# mainBoard_GTernal_1-1_v27.net
KiCad netlist of a schematic drawn in EAGLE
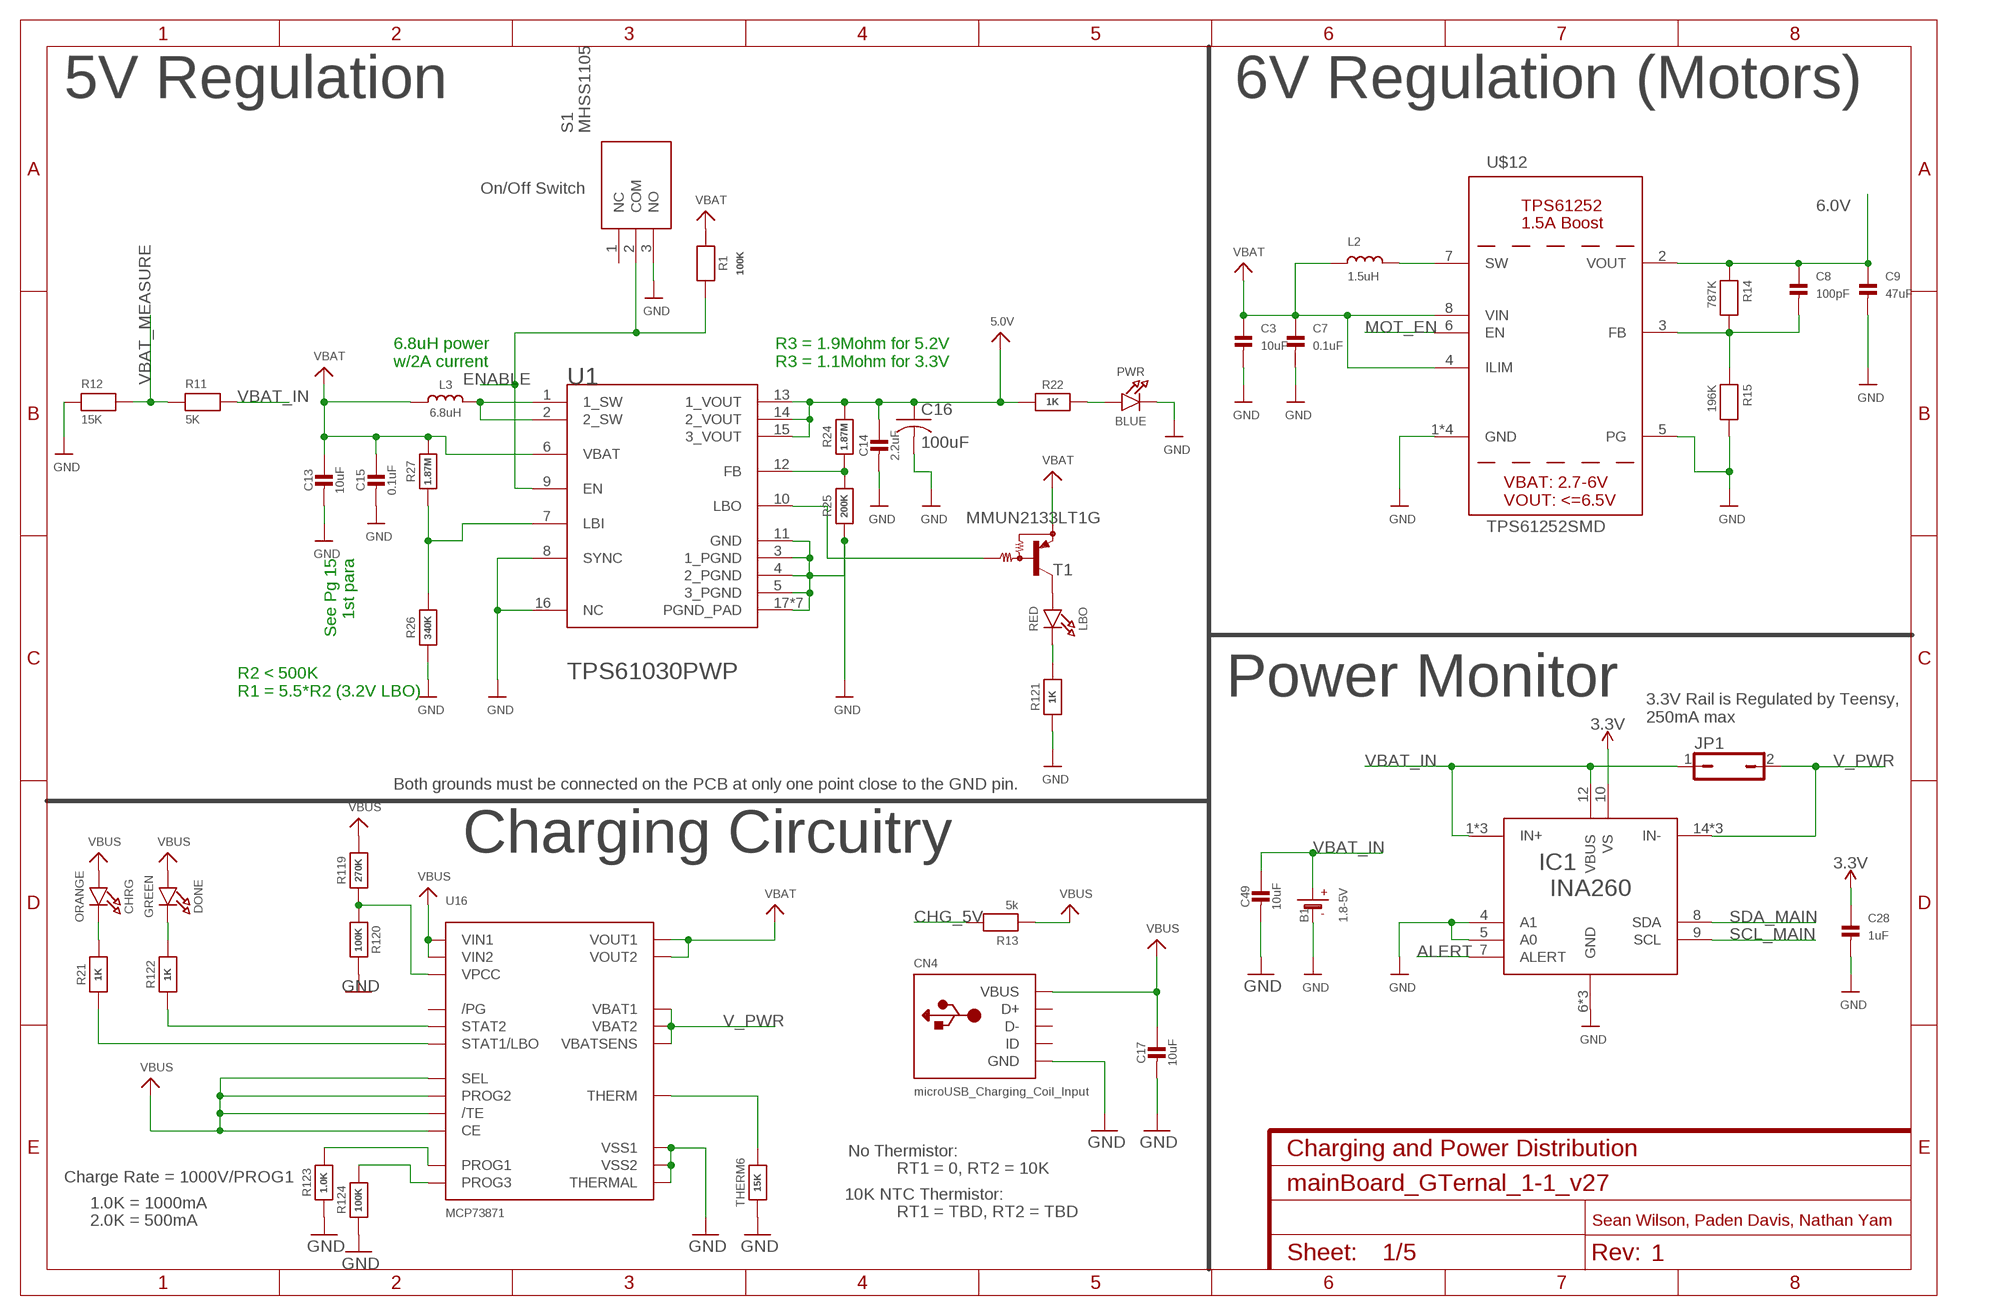
[diagram p0: schematic, sheet 1]
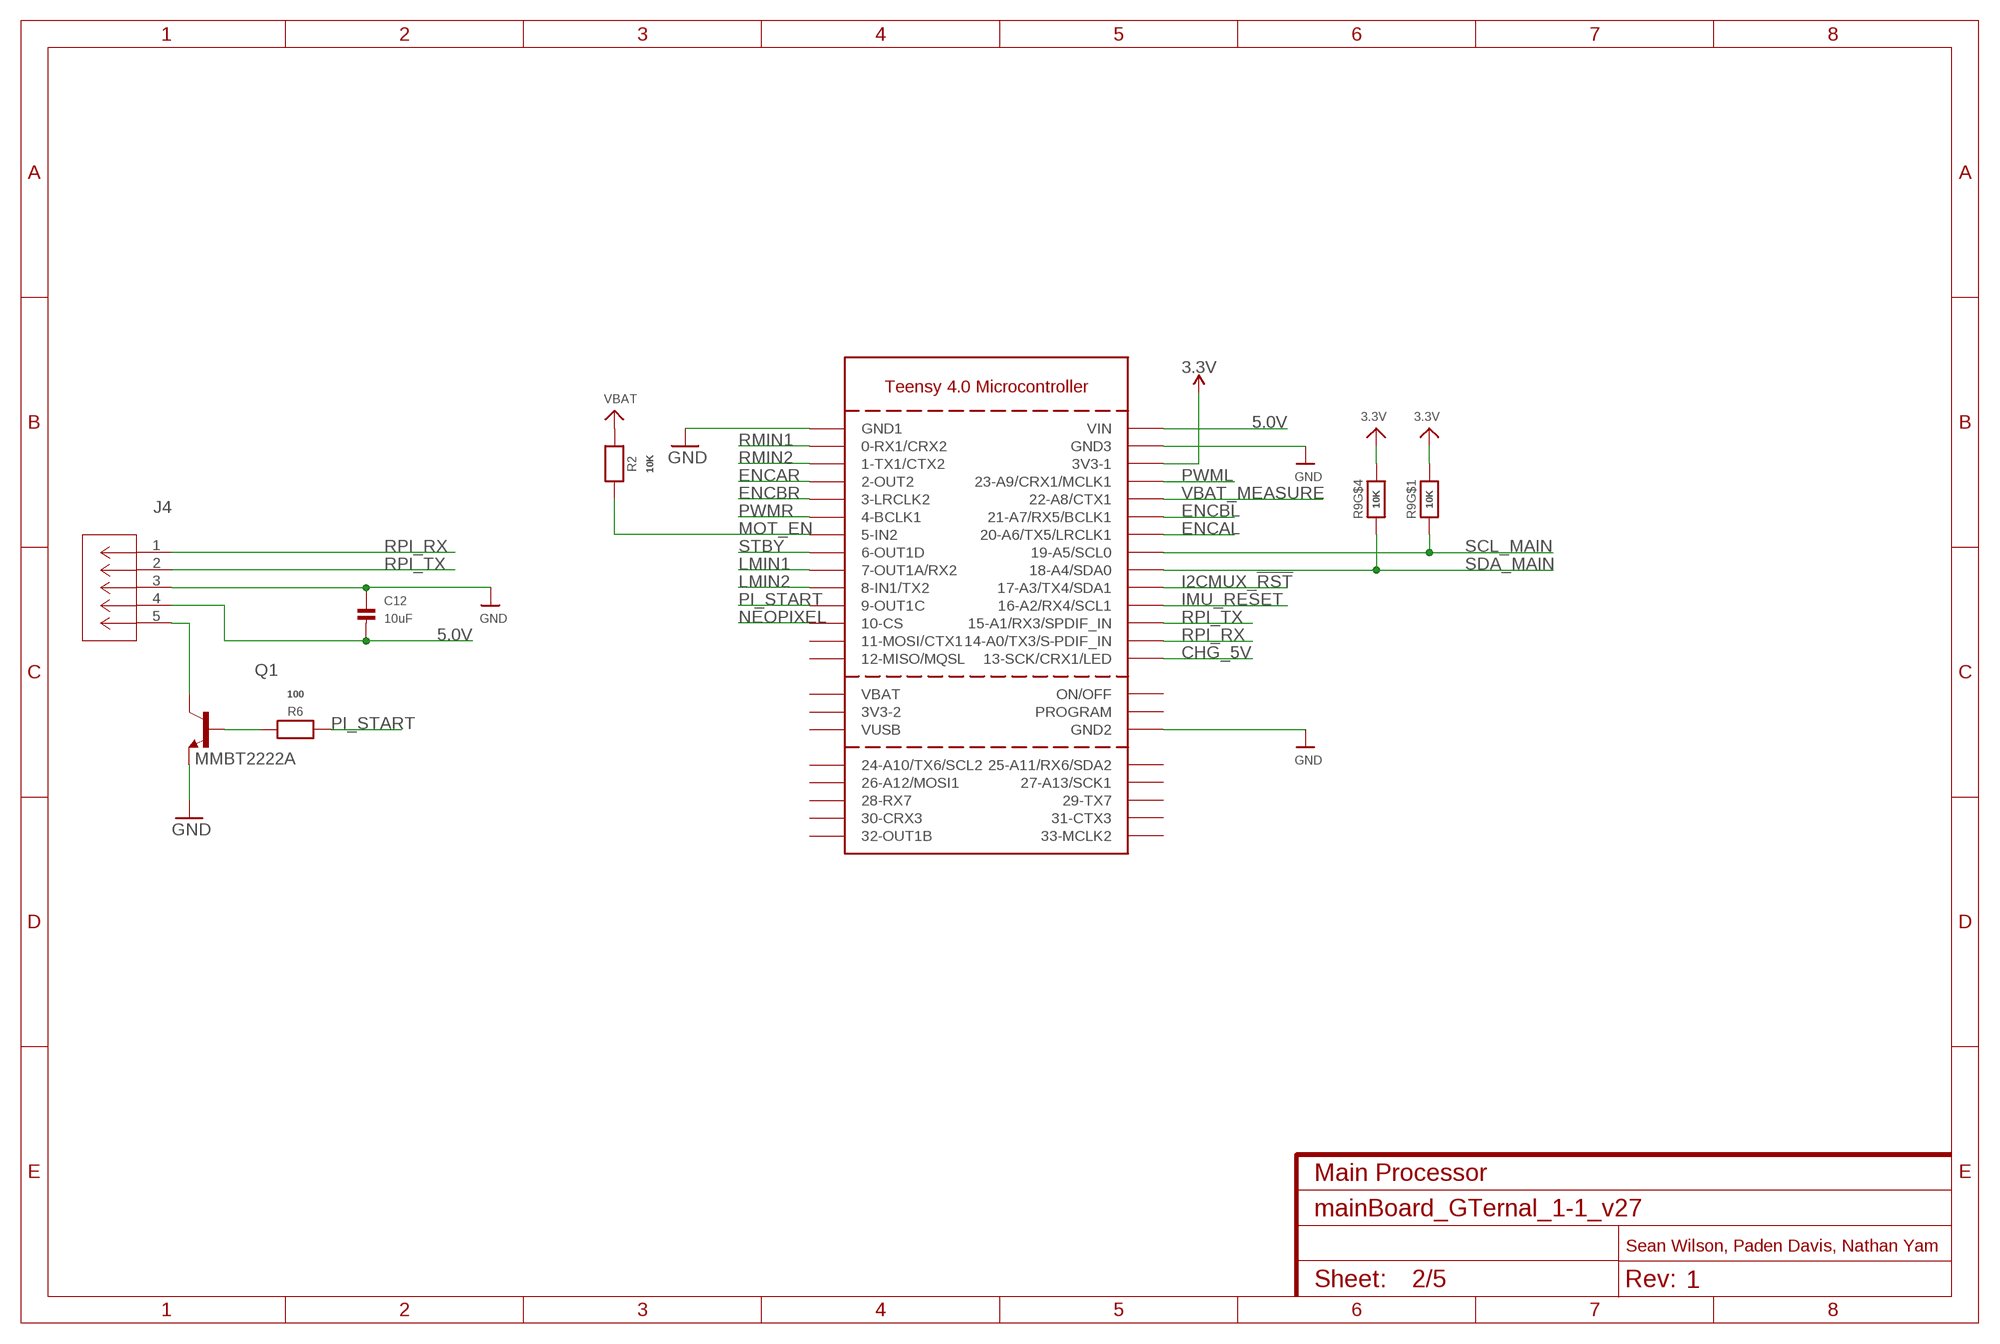
[diagram p1: schematic, sheet 2]
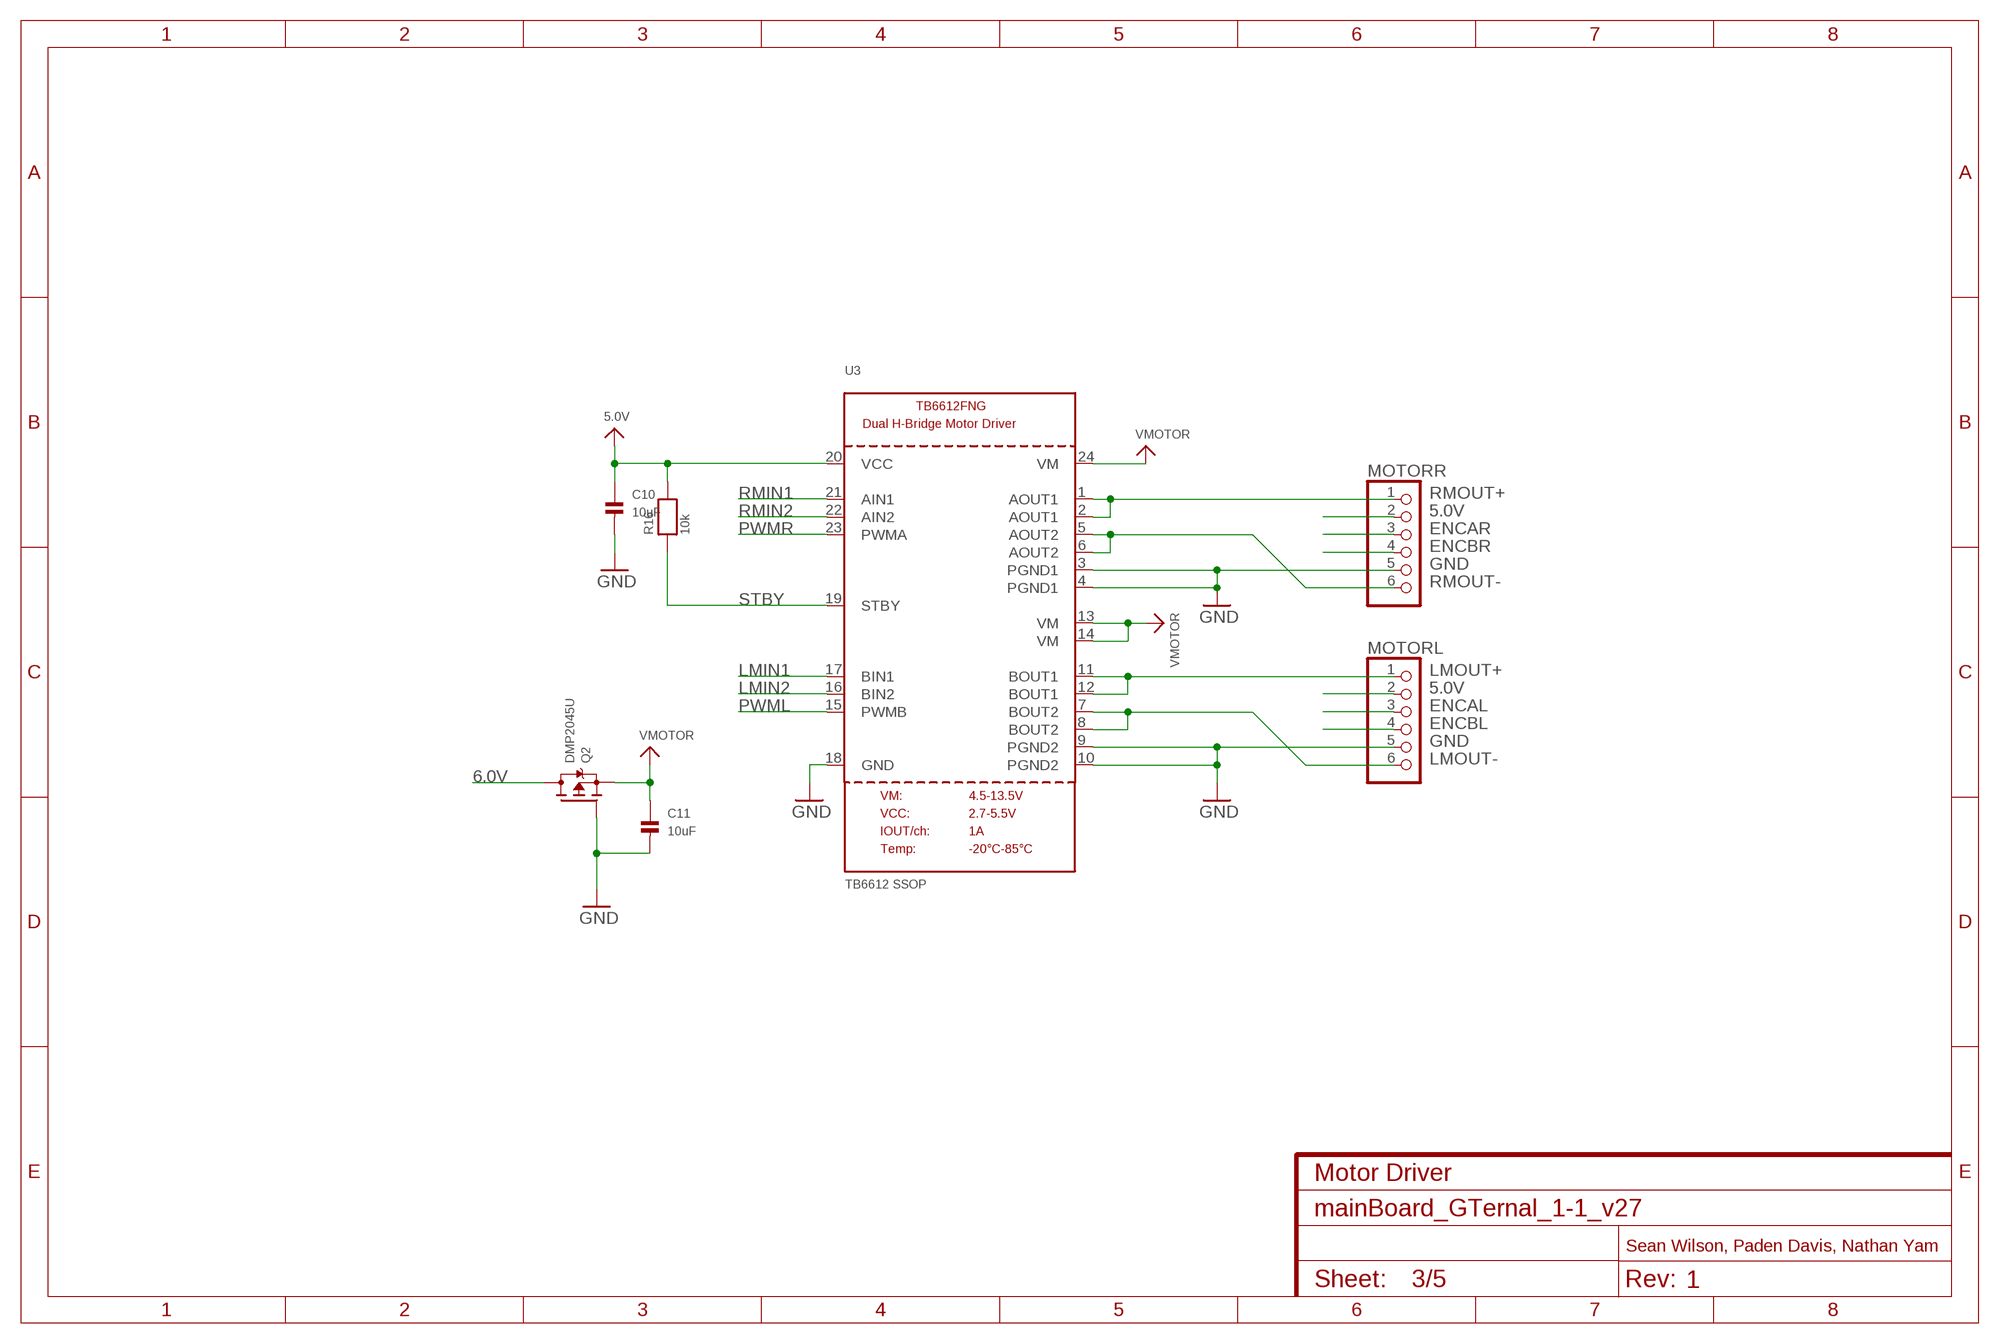
[diagram p2: schematic, sheet 3]
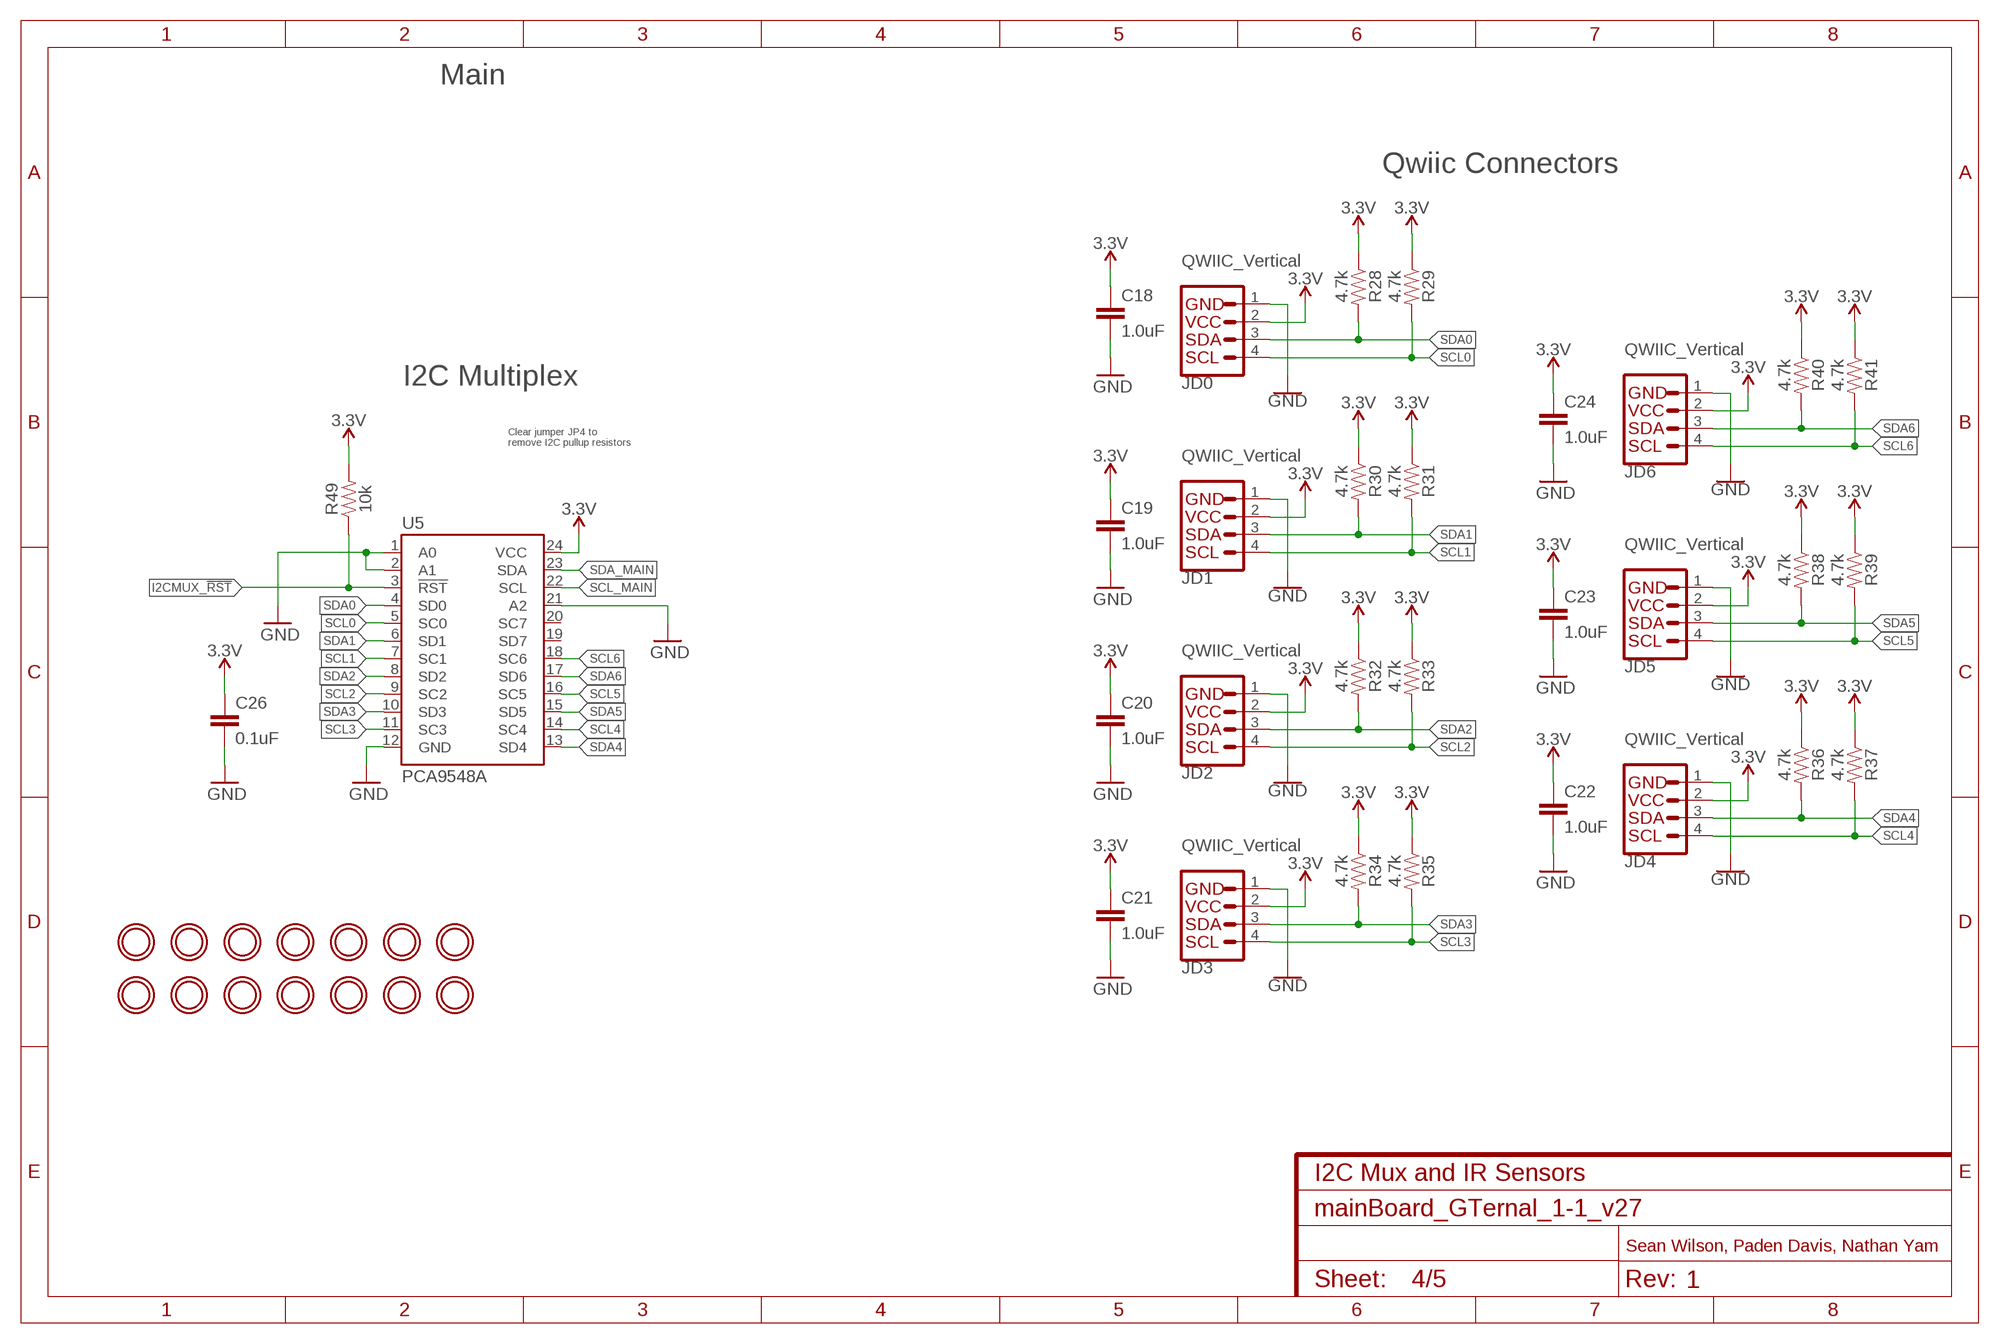
[diagram p3: schematic, sheet 4]
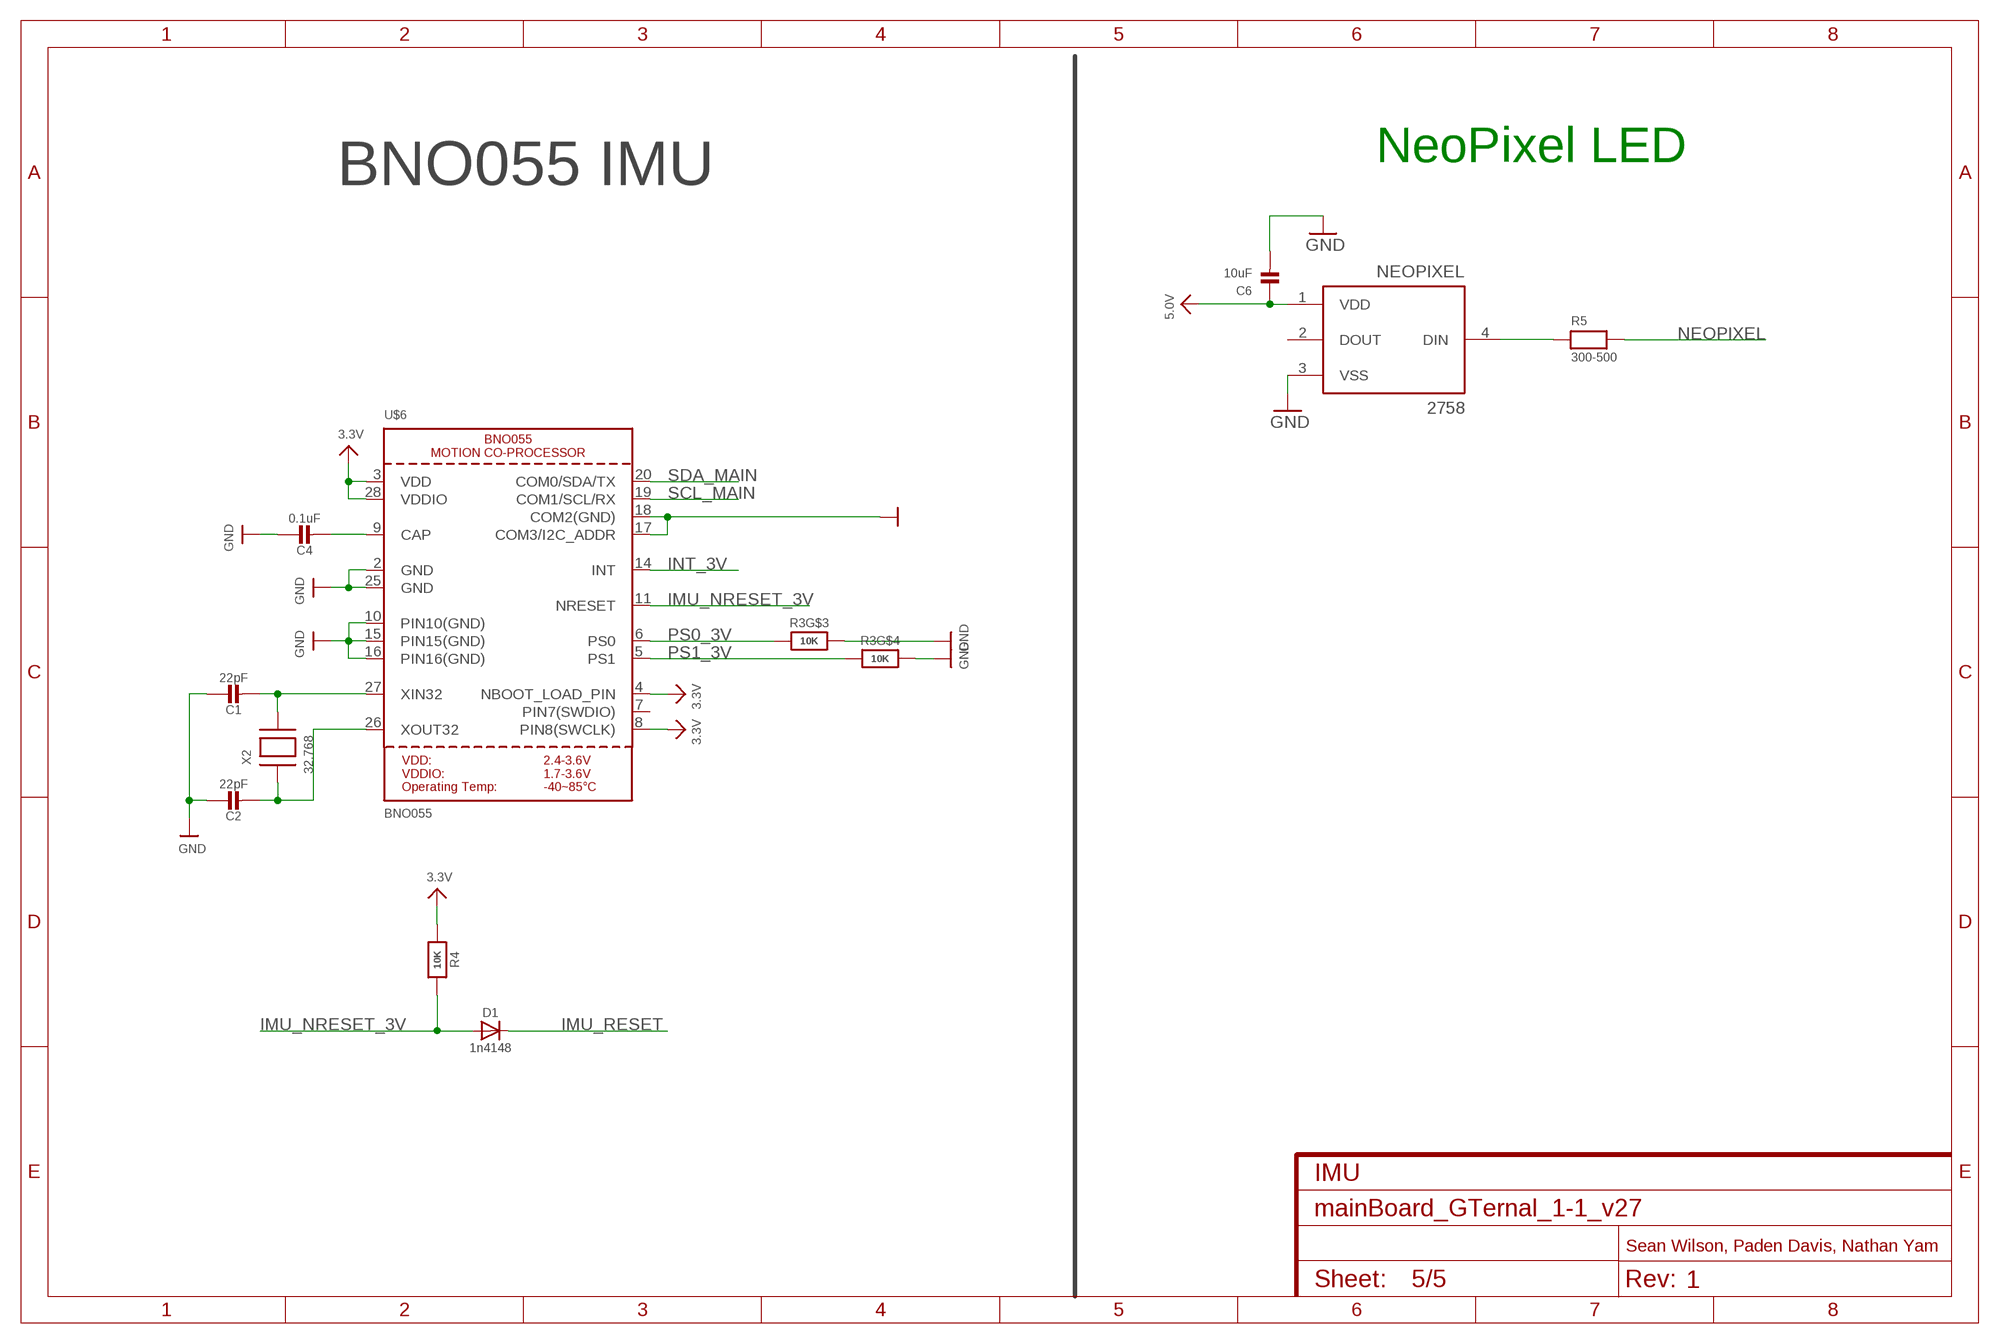
[diagram p4: schematic, sheet 5]

(export (version "E")
  (design (tool "Eeschema 10.0.6"))
  (components
    (comp (ref "C12")
      (value "10uF")
      (footprint "eagle-import:0603")
      (libsource (lib "eagle-import") (part "CAP_CERAMIC0603"))
    )
    (comp (ref "J4")
      (value "3A/250V")
      (footprint "eagle-import:CONN_B5B-XH-A_JST")
      (fields
        (field (name "MANUFACTURER_PART_NUMBER") "B5B-XH-A")
        (field (name "COPYRIGHT") "Copyright (C) 2023 Ultra Librarian. All rights reserved.")
      )
      (libsource (lib "eagle-import") (part "B5B-XH-ACONN_B5B-XH-A_JST"))
    )
    (comp (ref "Q1")
      (value "MMBT2222A")
      (footprint "eagle-import:SOT23")
      (fields (field (name "MF") "Diotec Semiconductor"))
      (libsource (lib "eagle-import") (part "MMBT2222A"))
    )
    (comp (ref "R2")
      (value "10K")
      (footprint "eagle-import:0805-NO")
      (libsource (lib "eagle-import") (part "RESISTOR0805_NOOUTLINE"))
    )
    (comp (ref "R6")
      (value "100")
      (footprint "eagle-import:0805-NO")
      (libsource (lib "eagle-import") (part "RESISTOR0805_NOOUTLINE"))
    )
    (comp (ref "R9")
      (value "10K")
      (footprint "eagle-import:RESPACK_4X0603")
      (libsource (lib "eagle-import") (part "RESISTOR_4PACK"))
    )
    (comp (ref "U$57")
      (value "TEENSY40")
      (footprint "eagle-import:TEENSY40")
      (libsource (lib "eagle-import") (part "TEENSY40"))
    )
    (comp (ref "C1")
      (value "22pF")
      (footprint "eagle-import:0603-NO")
      (libsource (lib "eagle-import") (part "CAP_CERAMIC0603_NO"))
    )
    (comp (ref "C2")
      (value "22pF")
      (footprint "eagle-import:0603-NO")
      (libsource (lib "eagle-import") (part "CAP_CERAMIC0603_NO"))
    )
    (comp (ref "C4")
      (value "0.1uF")
      (footprint "eagle-import:0603-NO")
      (libsource (lib "eagle-import") (part "CAP_CERAMIC0603_NO"))
    )
    (comp (ref "C6")
      (value "10uF")
      (footprint "eagle-import:0603")
      (libsource (lib "eagle-import") (part "CAP_CERAMIC0603"))
    )
    (comp (ref "D1")
      (value "1n4148")
      (footprint "eagle-import:SOD-323")
      (libsource (lib "eagle-import") (part "DIODESOD-323"))
    )
    (comp (ref "NEOPIXEL")
      (value "2758")
      (footprint "eagle-import:SOL320P540X170-4N")
      (fields (field (name "MF") "Adafruit Industries"))
      (libsource (lib "eagle-import") (part "2758"))
    )
    (comp (ref "R3")
      (value "10K")
      (footprint "eagle-import:RESPACK_4X0603")
      (libsource (lib "eagle-import") (part "RESISTOR_4PACK"))
    )
    (comp (ref "R4")
      (value "10K")
      (footprint "eagle-import:0603-NO")
      (libsource (lib "eagle-import") (part "RESISTOR_0603_NOOUT"))
    )
    (comp (ref "R5")
      (value "300-500")
      (footprint "eagle-import:0805")
      (libsource (lib "eagle-import") (part "RESISTOR0805"))
    )
    (comp (ref "U$6")
      (value "BNO055")
      (footprint "eagle-import:BNO055")
      (libsource (lib "eagle-import") (part "BNO055"))
    )
    (comp (ref "X2")
      (value "32.768")
      (footprint "eagle-import:XTAL3215")
      (libsource (lib "eagle-import") (part "XTAL-3.2X1.5"))
    )
    (comp (ref "B1")
      (value "1.8-5V")
      (footprint "eagle-import:JSTPH2")
      (libsource (lib "eagle-import") (part "BATTERY"))
    )
    (comp (ref "C3")
      (value "10uF")
      (footprint "eagle-import:0603")
      (libsource (lib "eagle-import") (part "CAP_CERAMIC0603"))
    )
    (comp (ref "C7")
      (value "0.1uF")
      (footprint "eagle-import:0805")
      (libsource (lib "eagle-import") (part "CAP_CERAMIC0805"))
    )
    (comp (ref "C8")
      (value "100pF")
      (footprint "eagle-import:0603")
      (libsource (lib "eagle-import") (part "CAP_CERAMIC0603"))
    )
    (comp (ref "C9")
      (value "47uF")
      (footprint "eagle-import:1206")
      (libsource (lib "eagle-import") (part "CAP_CERAMIC1206"))
    )
    (comp (ref "C13")
      (value "10uF")
      (footprint "eagle-import:0805-NO")
      (libsource (lib "eagle-import") (part "CAP_CERAMIC0805-NOOUTLINE"))
    )
    (comp (ref "C14")
      (value "2.2uF")
      (footprint "eagle-import:0805-NO")
      (libsource (lib "eagle-import") (part "CAP_CERAMIC0805-NOOUTLINE"))
    )
    (comp (ref "C15")
      (value "0.1uF")
      (footprint "eagle-import:0805_10MGAP")
      (libsource (lib "eagle-import") (part "CAP_CERAMIC0805_10MGAP"))
    )
    (comp (ref "C16")
      (value "100uF")
      (footprint "eagle-import:C1210")
      (libsource (lib "eagle-import") (part "C-USC1210"))
    )
    (comp (ref "C17")
      (value "10uF")
      (footprint "eagle-import:0805-NO")
      (libsource (lib "eagle-import") (part "CAP_CERAMIC0805-NOOUTLINE"))
    )
    (comp (ref "C28")
      (value "1uF")
      (footprint "eagle-import:0603-NO")
      (libsource (lib "eagle-import") (part "CAP_CERAMIC0603_NO"))
    )
    (comp (ref "C49")
      (value "10uF")
      (footprint "eagle-import:0805-NO")
      (libsource (lib "eagle-import") (part "CAP_CERAMIC0805-NOOUTLINE"))
    )
    (comp (ref "CHRG")
      (value "ORANGE")
      (footprint "eagle-import:CHIPLED_0805_NOOUTLINE")
      (libsource (lib "eagle-import") (part "LED0805_NOOUTLINE"))
    )
    (comp (ref "CN4")
      (value "microUSB_Charging_Coil_Input")
      (footprint "eagle-import:4UCONN_20329")
      (libsource (lib "eagle-import") (part "USBMICRO_20329"))
    )
    (comp (ref "DONE")
      (value "GREEN")
      (footprint "eagle-import:CHIPLED_0805_NOOUTLINE")
      (libsource (lib "eagle-import") (part "LED0805_NOOUTLINE"))
    )
    (comp (ref "IC1")
      (value "INA260")
      (footprint "eagle-import:TSSOP16")
      (libsource (lib "eagle-import") (part "INA260"))
    )
    (comp (ref "JP1")
      (value "JP1Q")
      (footprint "eagle-import:JP1")
      (libsource (lib "eagle-import") (part "JP1Q"))
    )
    (comp (ref "L2")
      (value "1.5uH")
      (footprint "eagle-import:MURATA_DFE252012P-1R5M=P2")
      (libsource (lib "eagle-import") (part "MURATA_DFE252012P-1R5M=P2"))
    )
    (comp (ref "L3")
      (value "6.8uH")
      (footprint "eagle-import:INDUCTOR_5X5MM_TDK_VLC5045")
      (libsource (lib "eagle-import") (part "INDUCTORTDK_VLC5045"))
    )
    (comp (ref "LBO")
      (value "RED")
      (footprint "eagle-import:CHIPLED_0805_NOOUTLINE")
      (libsource (lib "eagle-import") (part "LED0805_NOOUTLINE"))
    )
    (comp (ref "PWR")
      (value "BLUE")
      (footprint "eagle-import:CHIPLED_0805_NOOUTLINE")
      (libsource (lib "eagle-import") (part "LED0805_NOOUTLINE"))
    )
    (comp (ref "R1")
      (value "100K")
      (footprint "eagle-import:0805-NO")
      (libsource (lib "eagle-import") (part "RESISTOR0805_NOOUTLINE"))
    )
    (comp (ref "R11")
      (value "5K")
      (footprint "eagle-import:0805")
      (libsource (lib "eagle-import") (part "RESISTOR0805"))
    )
    (comp (ref "R12")
      (value "15K")
      (footprint "eagle-import:0805")
      (libsource (lib "eagle-import") (part "RESISTOR0805"))
    )
    (comp (ref "R13")
      (value "5k")
      (footprint "eagle-import:0805")
      (libsource (lib "eagle-import") (part "RESISTOR0805"))
    )
    (comp (ref "R14")
      (value "787K")
      (footprint "eagle-import:0805")
      (libsource (lib "eagle-import") (part "RESISTOR0805"))
    )
    (comp (ref "R15")
      (value "196K")
      (footprint "eagle-import:0805")
      (libsource (lib "eagle-import") (part "RESISTOR0805"))
    )
    (comp (ref "R21")
      (value "1K")
      (footprint "eagle-import:0805-NO")
      (libsource (lib "eagle-import") (part "RESISTOR0805_NOOUTLINE"))
    )
    (comp (ref "R22")
      (value "1K")
      (footprint "eagle-import:0805-NO")
      (libsource (lib "eagle-import") (part "RESISTOR0805_NOOUTLINE"))
    )
    (comp (ref "R24")
      (value "1.87M")
      (footprint "eagle-import:0805-NO")
      (libsource (lib "eagle-import") (part "RESISTOR0805_NOOUTLINE"))
    )
    (comp (ref "R25")
      (value "200K")
      (footprint "eagle-import:0805-NO")
      (libsource (lib "eagle-import") (part "RESISTOR0805_NOOUTLINE"))
    )
    (comp (ref "R26")
      (value "340K")
      (footprint "eagle-import:_0805MP")
      (libsource (lib "eagle-import") (part "microbuilder_vf.jQhFfLl6SwyupizEU6PNDA_RESISTOR_0805MP"))
    )
    (comp (ref "R27")
      (value "1.87M")
      (footprint "eagle-import:_0805MP")
      (libsource (lib "eagle-import") (part "microbuilder_vf.jQhFfLl6SwyupizEU6PNDA_RESISTOR_0805MP"))
    )
    (comp (ref "R119")
      (value "270K")
      (footprint "eagle-import:0805-NO")
      (libsource (lib "eagle-import") (part "RESISTOR0805_NOOUTLINE"))
    )
    (comp (ref "R120")
      (value "100K")
      (footprint "eagle-import:0805-NO")
      (libsource (lib "eagle-import") (part "RESISTOR0805_NOOUTLINE"))
    )
    (comp (ref "R121")
      (value "1K")
      (footprint "eagle-import:0805-NO")
      (libsource (lib "eagle-import") (part "RESISTOR0805_NOOUTLINE"))
    )
    (comp (ref "R122")
      (value "1K")
      (footprint "eagle-import:0805-NO")
      (libsource (lib "eagle-import") (part "RESISTOR0805_NOOUTLINE"))
    )
    (comp (ref "R123")
      (value "1.0K")
      (footprint "eagle-import:0805-NO")
      (libsource (lib "eagle-import") (part "RESISTOR0805_NOOUTLINE"))
    )
    (comp (ref "R124")
      (value "100K")
      (footprint "eagle-import:0805-NO")
      (libsource (lib "eagle-import") (part "RESISTOR0805_NOOUTLINE"))
    )
    (comp (ref "S1")
      (value "MHSS1105")
      (footprint "eagle-import:MHSS1105")
      (fields (field (name "MOUSER_PART_NUMBER") "642-MHSS1105"))
      (libsource (lib "eagle-import") (part "MHSS1105"))
    )
    (comp (ref "T1")
      (value "MMUN2133LT1G")
      (footprint "eagle-import:SC59-BEC")
      (libsource (lib "eagle-import") (part "-PNP_DRIVER-SC59-BECMUN2114T1"))
    )
    (comp (ref "THERM6")
      (value "15K")
      (footprint "eagle-import:0805-NO")
      (libsource (lib "eagle-import") (part "RESISTOR0805_NOOUTLINE"))
    )
    (comp (ref "U$12")
      (value "TPS61252SMD")
      (footprint "eagle-import:TPS61252")
      (libsource (lib "eagle-import") (part "TPS61252SMD"))
    )
    (comp (ref "U1")
      (value "TEXAS_INSTRUMENTS_TPS61030PWPTEXAS_INSTRUMENTS_TPS61030PWP_0_0")
      (footprint "eagle-import:TEXAS_INSTRUMENTS_TPS61030PWP_0")
      (fields
        (field (name "DIGIKEY_PART_NUMBER") "296-27006-5-ND")
        (field (name "MF") "Texas Instruments")
        (field (name "MOUSER_PART_NUMBER") "595-TPS61030PWP")
      )
      (libsource (lib "eagle-import") (part "TEXAS_INSTRUMENTS_TPS61030PWPTEXAS_INSTRUMENTS_TPS61030PWP_0_0"))
    )
    (comp (ref "U16")
      (value "MCP73871")
      (footprint "eagle-import:QFN20_4MM")
      (libsource (lib "eagle-import") (part "MCP73871"))
    )
    (comp (ref "C18")
      (value "1.0uF")
      (footprint "eagle-import:0603")
      (libsource (lib "eagle-import") (part "1.0UF-0603-16V-10%"))
    )
    (comp (ref "C19")
      (value "1.0uF")
      (footprint "eagle-import:0603")
      (libsource (lib "eagle-import") (part "1.0UF-0603-16V-10%"))
    )
    (comp (ref "C20")
      (value "1.0uF")
      (footprint "eagle-import:0603")
      (libsource (lib "eagle-import") (part "1.0UF-0603-16V-10%"))
    )
    (comp (ref "C21")
      (value "1.0uF")
      (footprint "eagle-import:0603")
      (libsource (lib "eagle-import") (part "1.0UF-0603-16V-10%"))
    )
    (comp (ref "C22")
      (value "1.0uF")
      (footprint "eagle-import:0603")
      (libsource (lib "eagle-import") (part "1.0UF-0603-16V-10%"))
    )
    (comp (ref "C23")
      (value "1.0uF")
      (footprint "eagle-import:0603")
      (libsource (lib "eagle-import") (part "1.0UF-0603-16V-10%"))
    )
    (comp (ref "C24")
      (value "1.0uF")
      (footprint "eagle-import:0603")
      (libsource (lib "eagle-import") (part "1.0UF-0603-16V-10%"))
    )
    (comp (ref "C26")
      (value "0.1uF")
      (footprint "eagle-import:0603")
      (libsource (lib "eagle-import") (part "0.1UF-0603-25V-(+80/-20%)"))
    )
    (comp (ref "JD0")
      (value "QWIIC_Vertical")
      (footprint "eagle-import:JST04_1MM_VERT")
      (libsource (lib "eagle-import") (part "QWIIC_CONNECTOR"))
    )
    (comp (ref "JD1")
      (value "QWIIC_Vertical")
      (footprint "eagle-import:JST04_1MM_VERT")
      (libsource (lib "eagle-import") (part "QWIIC_CONNECTOR"))
    )
    (comp (ref "JD2")
      (value "QWIIC_Vertical")
      (footprint "eagle-import:JST04_1MM_VERT")
      (libsource (lib "eagle-import") (part "QWIIC_CONNECTOR"))
    )
    (comp (ref "JD3")
      (value "QWIIC_Vertical")
      (footprint "eagle-import:JST04_1MM_VERT")
      (libsource (lib "eagle-import") (part "QWIIC_CONNECTOR"))
    )
    (comp (ref "JD4")
      (value "QWIIC_Vertical")
      (footprint "eagle-import:JST04_1MM_VERT")
      (libsource (lib "eagle-import") (part "QWIIC_CONNECTOR"))
    )
    (comp (ref "JD5")
      (value "QWIIC_Vertical")
      (footprint "eagle-import:JST04_1MM_VERT")
      (libsource (lib "eagle-import") (part "QWIIC_CONNECTOR"))
    )
    (comp (ref "JD6")
      (value "QWIIC_Vertical")
      (footprint "eagle-import:JST04_1MM_VERT")
      (libsource (lib "eagle-import") (part "QWIIC_CONNECTOR"))
    )
    (comp (ref "R28")
      (value "4.7k")
      (footprint "eagle-import:0603")
      (libsource (lib "eagle-import") (part "4.7KOHM-0603-1/10W-1%"))
    )
    (comp (ref "R29")
      (value "4.7k")
      (footprint "eagle-import:0603")
      (libsource (lib "eagle-import") (part "4.7KOHM-0603-1/10W-1%"))
    )
    (comp (ref "R30")
      (value "4.7k")
      (footprint "eagle-import:0603")
      (libsource (lib "eagle-import") (part "4.7KOHM-0603-1/10W-1%"))
    )
    (comp (ref "R31")
      (value "4.7k")
      (footprint "eagle-import:0603")
      (libsource (lib "eagle-import") (part "4.7KOHM-0603-1/10W-1%"))
    )
    (comp (ref "R32")
      (value "4.7k")
      (footprint "eagle-import:0603")
      (libsource (lib "eagle-import") (part "4.7KOHM-0603-1/10W-1%"))
    )
    (comp (ref "R33")
      (value "4.7k")
      (footprint "eagle-import:0603")
      (libsource (lib "eagle-import") (part "4.7KOHM-0603-1/10W-1%"))
    )
    (comp (ref "R34")
      (value "4.7k")
      (footprint "eagle-import:0603")
      (libsource (lib "eagle-import") (part "4.7KOHM-0603-1/10W-1%"))
    )
    (comp (ref "R35")
      (value "4.7k")
      (footprint "eagle-import:0603")
      (libsource (lib "eagle-import") (part "4.7KOHM-0603-1/10W-1%"))
    )
    (comp (ref "R36")
      (value "4.7k")
      (footprint "eagle-import:0603")
      (libsource (lib "eagle-import") (part "4.7KOHM-0603-1/10W-1%"))
    )
    (comp (ref "R37")
      (value "4.7k")
      (footprint "eagle-import:0603")
      (libsource (lib "eagle-import") (part "4.7KOHM-0603-1/10W-1%"))
    )
    (comp (ref "R38")
      (value "4.7k")
      (footprint "eagle-import:0603")
      (libsource (lib "eagle-import") (part "4.7KOHM-0603-1/10W-1%"))
    )
    (comp (ref "R39")
      (value "4.7k")
      (footprint "eagle-import:0603")
      (libsource (lib "eagle-import") (part "4.7KOHM-0603-1/10W-1%"))
    )
    (comp (ref "R40")
      (value "4.7k")
      (footprint "eagle-import:0603")
      (libsource (lib "eagle-import") (part "4.7KOHM-0603-1/10W-1%"))
    )
    (comp (ref "R41")
      (value "4.7k")
      (footprint "eagle-import:0603")
      (libsource (lib "eagle-import") (part "4.7KOHM-0603-1/10W-1%"))
    )
    (comp (ref "R49")
      (value "10k")
      (footprint "eagle-import:0603")
      (libsource (lib "eagle-import") (part "10KOHM-0603-1/10W-1%"))
    )
    (comp (ref "U$8")
      (value "MOUNTINGHOLE2.5")
      (footprint "eagle-import:MOUNTINGHOLE_2.5_PLATED")
      (libsource (lib "eagle-import") (part "MOUNTINGHOLE2.5"))
    )
    (comp (ref "U$30")
      (value "MOUNTINGHOLE2.5")
      (footprint "eagle-import:MOUNTINGHOLE_2.5_PLATED")
      (libsource (lib "eagle-import") (part "MOUNTINGHOLE2.5"))
    )
    (comp (ref "U$31")
      (value "MOUNTINGHOLE2.5")
      (footprint "eagle-import:MOUNTINGHOLE_2.5_PLATED")
      (libsource (lib "eagle-import") (part "MOUNTINGHOLE2.5"))
    )
    (comp (ref "U$32")
      (value "MOUNTINGHOLE2.5")
      (footprint "eagle-import:MOUNTINGHOLE_2.5_PLATED")
      (libsource (lib "eagle-import") (part "MOUNTINGHOLE2.5"))
    )
    (comp (ref "U$33")
      (value "MOUNTINGHOLE2.5")
      (footprint "eagle-import:MOUNTINGHOLE_2.5_PLATED")
      (libsource (lib "eagle-import") (part "MOUNTINGHOLE2.5"))
    )
    (comp (ref "U$34")
      (value "MOUNTINGHOLE2.5")
      (footprint "eagle-import:MOUNTINGHOLE_2.5_PLATED")
      (libsource (lib "eagle-import") (part "MOUNTINGHOLE2.5"))
    )
    (comp (ref "U$35")
      (value "MOUNTINGHOLE2.5")
      (footprint "eagle-import:MOUNTINGHOLE_2.5_PLATED")
      (libsource (lib "eagle-import") (part "MOUNTINGHOLE2.5"))
    )
    (comp (ref "U$36")
      (value "MOUNTINGHOLE2.5")
      (footprint "eagle-import:MOUNTINGHOLE_2.5_PLATED")
      (libsource (lib "eagle-import") (part "MOUNTINGHOLE2.5"))
    )
    (comp (ref "U$37")
      (value "MOUNTINGHOLE2.5")
      (footprint "eagle-import:MOUNTINGHOLE_2.5_PLATED")
      (libsource (lib "eagle-import") (part "MOUNTINGHOLE2.5"))
    )
    (comp (ref "U$43")
      (value "MOUNTINGHOLE2.5")
      (footprint "eagle-import:MOUNTINGHOLE_2.5_PLATED")
      (libsource (lib "eagle-import") (part "MOUNTINGHOLE2.5"))
    )
    (comp (ref "U$45")
      (value "MOUNTINGHOLE2.5")
      (footprint "eagle-import:MOUNTINGHOLE_2.5_PLATED")
      (libsource (lib "eagle-import") (part "MOUNTINGHOLE2.5"))
    )
    (comp (ref "U$46")
      (value "MOUNTINGHOLE2.5")
      (footprint "eagle-import:MOUNTINGHOLE_2.5_PLATED")
      (libsource (lib "eagle-import") (part "MOUNTINGHOLE2.5"))
    )
    (comp (ref "U$47")
      (value "MOUNTINGHOLE2.5")
      (footprint "eagle-import:MOUNTINGHOLE_2.5_PLATED")
      (libsource (lib "eagle-import") (part "MOUNTINGHOLE2.5"))
    )
    (comp (ref "U$48")
      (value "MOUNTINGHOLE2.5")
      (footprint "eagle-import:MOUNTINGHOLE_2.5_PLATED")
      (libsource (lib "eagle-import") (part "MOUNTINGHOLE2.5"))
    )
    (comp (ref "U5")
      (value "PCA9548A")
      (footprint "eagle-import:TSSOP28")
      (libsource (lib "eagle-import") (part "PCA9548A"))
    )
    (comp (ref "C10")
      (value "10uF")
      (footprint "eagle-import:0603")
      (libsource (lib "eagle-import") (part "CAP_CERAMIC0603"))
    )
    (comp (ref "C11")
      (value "10uF")
      (footprint "eagle-import:0603")
      (libsource (lib "eagle-import") (part "CAP_CERAMIC0603"))
    )
    (comp (ref "MOTORL")
      (value "PINHD-1X6CB")
      (footprint "eagle-import:1X06-CLEANBIG")
      (libsource (lib "eagle-import") (part "PINHD-1X6CB"))
    )
    (comp (ref "MOTORR")
      (value "PINHD-1X6CB")
      (footprint "eagle-import:1X06-CLEANBIG")
      (libsource (lib "eagle-import") (part "PINHD-1X6CB"))
    )
    (comp (ref "Q2")
      (value "DMP2045U")
      (footprint "eagle-import:SOT23-WIDE")
      (libsource (lib "eagle-import") (part "MOSFET-PWIDE"))
    )
    (comp (ref "R16")
      (value "10k")
      (footprint "eagle-import:0805")
      (libsource (lib "eagle-import") (part "RESISTOR0805"))
    )
    (comp (ref "U3")
      (value "TB6612 SSOP")
      (footprint "eagle-import:SSOP24")
      (libsource (lib "eagle-import") (part "TB6612FNGSSOP"))
    )
  )
  (nets
    (net (code "1") (name "3.3V") (class "Default")
      (node (ref "C18") (pin "1") (pinfunction "1_1") (pintype "passive"))
      (node (ref "C19") (pin "1") (pinfunction "1_1") (pintype "passive"))
      (node (ref "C20") (pin "1") (pinfunction "1_1") (pintype "passive"))
      (node (ref "C21") (pin "1") (pinfunction "1_1") (pintype "passive"))
      (node (ref "C22") (pin "1") (pinfunction "1_1") (pintype "passive"))
      (node (ref "C23") (pin "1") (pinfunction "1_1") (pintype "passive"))
      (node (ref "C24") (pin "1") (pinfunction "1_1") (pintype "passive"))
      (node (ref "C26") (pin "1") (pinfunction "1_1") (pintype "passive"))
      (node (ref "C28") (pin "1") (pinfunction "1_1") (pintype "passive"))
      (node (ref "IC1") (pin "10") (pinfunction "VS_10") (pintype "power_in"))
      (node (ref "JD0") (pin "2") (pinfunction "2_2") (pintype "power_in"))
      (node (ref "JD1") (pin "2") (pinfunction "2_2") (pintype "power_in"))
      (node (ref "JD2") (pin "2") (pinfunction "2_2") (pintype "power_in"))
      (node (ref "JD3") (pin "2") (pinfunction "2_2") (pintype "power_in"))
      (node (ref "JD4") (pin "2") (pinfunction "2_2") (pintype "power_in"))
      (node (ref "JD5") (pin "2") (pinfunction "2_2") (pintype "power_in"))
      (node (ref "JD6") (pin "2") (pinfunction "2_2") (pintype "power_in"))
      (node (ref "R28") (pin "1") (pinfunction "1_1") (pintype "passive"))
      (node (ref "R29") (pin "1") (pinfunction "1_1") (pintype "passive"))
      (node (ref "R30") (pin "1") (pinfunction "1_1") (pintype "passive"))
      (node (ref "R31") (pin "1") (pinfunction "1_1") (pintype "passive"))
      (node (ref "R32") (pin "1") (pinfunction "1_1") (pintype "passive"))
      (node (ref "R33") (pin "1") (pinfunction "1_1") (pintype "passive"))
      (node (ref "R34") (pin "1") (pinfunction "1_1") (pintype "passive"))
      (node (ref "R35") (pin "1") (pinfunction "1_1") (pintype "passive"))
      (node (ref "R36") (pin "1") (pinfunction "1_1") (pintype "passive"))
      (node (ref "R37") (pin "1") (pinfunction "1_1") (pintype "passive"))
      (node (ref "R38") (pin "1") (pinfunction "1_1") (pintype "passive"))
      (node (ref "R39") (pin "1") (pinfunction "1_1") (pintype "passive"))
      (node (ref "R4") (pin "1") (pinfunction "1_1") (pintype "passive"))
      (node (ref "R40") (pin "1") (pinfunction "1_1") (pintype "passive"))
      (node (ref "R41") (pin "1") (pinfunction "1_1") (pintype "passive"))
      (node (ref "R49") (pin "2") (pinfunction "2_2") (pintype "passive"))
      (node (ref "R9") (pin "1") (pinfunction "1_1") (pintype "passive"))
      (node (ref "R9") (pin "4") (pinfunction "1_4") (pintype "passive"))
      (node (ref "U$57") (pin "3V3-1") (pinfunction "3V3-1_3V3-1") (pintype "bidirectional"))
      (node (ref "U$6") (pin "28") (pinfunction "VDDIO_28") (pintype "power_in"))
      (node (ref "U$6") (pin "3") (pinfunction "VDD_3") (pintype "power_in"))
      (node (ref "U$6") (pin "4") (pinfunction "NBOOT_LOAD_PIN_4") (pintype "bidirectional"))
      (node (ref "U$6") (pin "8") (pinfunction "PIN8(SWCLK)_8") (pintype "bidirectional"))
      (node (ref "U5") (pin "24") (pinfunction "VCC_24") (pintype "bidirectional"))
    )
    (net (code "2") (name "5.0V") (class "Default")
      (node (ref "C10") (pin "1") (pinfunction "P$1_1") (pintype "passive"))
      (node (ref "C12") (pin "2") (pinfunction "P$2_2") (pintype "passive"))
      (node (ref "C14") (pin "1") (pinfunction "1_1") (pintype "passive"))
      (node (ref "C16") (pin "1") (pinfunction "1_1") (pintype "passive"))
      (node (ref "C6") (pin "1") (pinfunction "P$1_1") (pintype "passive"))
      (node (ref "J4") (pin "4") (pinfunction "4_4") (pintype "passive"))
      (node (ref "MOTORL") (pin "2") (pinfunction "2_2") (pintype "passive"))
      (node (ref "MOTORR") (pin "2") (pinfunction "2_2") (pintype "passive"))
      (node (ref "NEOPIXEL") (pin "1") (pinfunction "VDD_1") (pintype "power_in"))
      (node (ref "R16") (pin "2") (pinfunction "2_2") (pintype "passive"))
      (node (ref "R22") (pin "1") (pinfunction "1_1") (pintype "passive"))
      (node (ref "R24") (pin "2") (pinfunction "2_2") (pintype "passive"))
      (node (ref "U$57") (pin "VIN") (pinfunction "VIN_VIN") (pintype "bidirectional"))
      (node (ref "U1") (pin "13") (pinfunction "1_VOUT_13") (pintype "bidirectional"))
      (node (ref "U1") (pin "14") (pinfunction "2_VOUT_14") (pintype "bidirectional"))
      (node (ref "U1") (pin "15") (pinfunction "3_VOUT_15") (pintype "bidirectional"))
      (node (ref "U3") (pin "20") (pinfunction "VCC_20") (pintype "power_in"))
    )
    (net (code "3") (name "6.0V") (class "Default")
      (node (ref "C8") (pin "1") (pinfunction "P$1_1") (pintype "passive"))
      (node (ref "C9") (pin "1") (pinfunction "P$1_1") (pintype "passive"))
      (node (ref "Q2") (pin "3") (pinfunction "D_3") (pintype "passive"))
      (node (ref "R14") (pin "1") (pinfunction "1_1") (pintype "passive"))
      (node (ref "U$12") (pin "2") (pinfunction "VOUT_2") (pintype "bidirectional"))
    )
    (net (code "4") (name "ALERT") (class "Default")
      (node (ref "IC1") (pin "7") (pinfunction "ALERT_7") (pintype "output"))
    )
    (net (code "5") (name "CHG_5V") (class "Default")
      (node (ref "R13") (pin "2") (pinfunction "2_2") (pintype "passive"))
      (node (ref "U$57") (pin "13-SCK/CRX1/LED") (pinfunction "13-SCK/CRX1/LED_13-SCK/CRX1/LED") (pintype "bidirectional"))
    )
    (net (code "6") (name "ENABLE") (class "Default")
      (node (ref "R1") (pin "2") (pinfunction "2_2") (pintype "passive"))
      (node (ref "S1") (pin "2") (pinfunction "COM_2") (pintype "bidirectional"))
      (node (ref "U1") (pin "9") (pinfunction "EN_9") (pintype "bidirectional"))
    )
    (net (code "7") (name "ENCAL") (class "Default")
      (node (ref "MOTORL") (pin "3") (pinfunction "3_3") (pintype "passive"))
      (node (ref "U$57") (pin "20-A6/TX5/LRCLK1") (pinfunction "20-A6/TX5/LRCLK1_20-A6/TX5/LRCLK1") (pintype "bidirectional"))
    )
    (net (code "8") (name "ENCAR") (class "Default")
      (node (ref "MOTORR") (pin "3") (pinfunction "3_3") (pintype "passive"))
      (node (ref "U$57") (pin "2-OUT2") (pinfunction "2-OUT2_2-OUT2") (pintype "bidirectional"))
    )
    (net (code "9") (name "ENCBL") (class "Default")
      (node (ref "MOTORL") (pin "4") (pinfunction "4_4") (pintype "passive"))
      (node (ref "U$57") (pin "21-A7/RX5/BCLK1") (pinfunction "21-A7/RX5/BCLK1_21-A7/RX5/BCLK1") (pintype "bidirectional"))
    )
    (net (code "10") (name "ENCBR") (class "Default")
      (node (ref "MOTORR") (pin "4") (pinfunction "4_4") (pintype "passive"))
      (node (ref "U$57") (pin "3-LRCLK2") (pinfunction "3-LRCLK2_3-LRCLK2") (pintype "bidirectional"))
    )
    (net (code "11") (name "GND") (class "Default")
      (node (ref "B1") (pin "1") (pinfunction "-_1") (pintype "passive"))
      (node (ref "C1") (pin "1") (pinfunction "1_1") (pintype "passive"))
      (node (ref "C10") (pin "2") (pinfunction "P$2_2") (pintype "passive"))
      (node (ref "C11") (pin "2") (pinfunction "P$2_2") (pintype "passive"))
      (node (ref "C12") (pin "1") (pinfunction "P$1_1") (pintype "passive"))
      (node (ref "C13") (pin "2") (pinfunction "2_2") (pintype "passive"))
      (node (ref "C14") (pin "2") (pinfunction "2_2") (pintype "passive"))
      (node (ref "C15") (pin "2") (pinfunction "2_2") (pintype "passive"))
      (node (ref "C16") (pin "2") (pinfunction "2_2") (pintype "passive"))
      (node (ref "C17") (pin "2") (pinfunction "2_2") (pintype "passive"))
      (node (ref "C18") (pin "2") (pinfunction "2_2") (pintype "passive"))
      (node (ref "C19") (pin "2") (pinfunction "2_2") (pintype "passive"))
      (node (ref "C2") (pin "1") (pinfunction "1_1") (pintype "passive"))
      (node (ref "C20") (pin "2") (pinfunction "2_2") (pintype "passive"))
      (node (ref "C21") (pin "2") (pinfunction "2_2") (pintype "passive"))
      (node (ref "C22") (pin "2") (pinfunction "2_2") (pintype "passive"))
      (node (ref "C23") (pin "2") (pinfunction "2_2") (pintype "passive"))
      (node (ref "C24") (pin "2") (pinfunction "2_2") (pintype "passive"))
      (node (ref "C26") (pin "2") (pinfunction "2_2") (pintype "passive"))
      (node (ref "C28") (pin "2") (pinfunction "2_2") (pintype "passive"))
      (node (ref "C3") (pin "2") (pinfunction "P$2_2") (pintype "passive"))
      (node (ref "C4") (pin "1") (pinfunction "1_1") (pintype "passive"))
      (node (ref "C49") (pin "2") (pinfunction "2_2") (pintype "passive"))
      (node (ref "C6") (pin "2") (pinfunction "P$2_2") (pintype "passive"))
      (node (ref "C7") (pin "2") (pinfunction "P$2_2") (pintype "passive"))
      (node (ref "C9") (pin "2") (pinfunction "P$2_2") (pintype "passive"))
      (node (ref "CN4") (pin "BASE@1") (pinfunction "GND_BASE@1") (pintype "power_in"))
      (node (ref "CN4") (pin "BASE@2") (pinfunction "GND_BASE@2") (pintype "power_in"))
      (node (ref "CN4") (pin "GND") (pinfunction "GND_GND") (pintype "power_in"))
      (node (ref "CN4") (pin "SPRT@1") (pinfunction "GND_SPRT@1") (pintype "power_in"))
      (node (ref "CN4") (pin "SPRT@2") (pinfunction "GND_SPRT@2") (pintype "power_in"))
      (node (ref "CN4") (pin "SPRT@3") (pinfunction "GND_SPRT@3") (pintype "power_in"))
      (node (ref "CN4") (pin "SPRT@4") (pinfunction "GND_SPRT@4") (pintype "power_in"))
      (node (ref "IC1") (pin "11") (pinfunction "GND_11") (pintype "power_in"))
      (node (ref "IC1") (pin "13") (pinfunction "GND_13") (pintype "power_in"))
      (node (ref "IC1") (pin "4") (pinfunction "A1_4") (pintype "input"))
      (node (ref "IC1") (pin "5") (pinfunction "A0_5") (pintype "input"))
      (node (ref "IC1") (pin "6") (pinfunction "GND_6") (pintype "power_in"))
      (node (ref "J4") (pin "3") (pinfunction "3_3") (pintype "passive"))
      (node (ref "JD0") (pin "1") (pinfunction "1_1") (pintype "power_in"))
      (node (ref "JD1") (pin "1") (pinfunction "1_1") (pintype "power_in"))
      (node (ref "JD2") (pin "1") (pinfunction "1_1") (pintype "power_in"))
      (node (ref "JD3") (pin "1") (pinfunction "1_1") (pintype "power_in"))
      (node (ref "JD4") (pin "1") (pinfunction "1_1") (pintype "power_in"))
      (node (ref "JD5") (pin "1") (pinfunction "1_1") (pintype "power_in"))
      (node (ref "JD6") (pin "1") (pinfunction "1_1") (pintype "power_in"))
      (node (ref "MOTORL") (pin "5") (pinfunction "5_5") (pintype "passive"))
      (node (ref "MOTORR") (pin "5") (pinfunction "5_5") (pintype "passive"))
      (node (ref "NEOPIXEL") (pin "3") (pinfunction "VSS_3") (pintype "power_in"))
      (node (ref "PWR") (pin "C") (pinfunction "C_C") (pintype "passive"))
      (node (ref "Q1") (pin "2") (pinfunction "E_2") (pintype "passive"))
      (node (ref "Q2") (pin "1") (pinfunction "G_1") (pintype "passive"))
      (node (ref "R12") (pin "1") (pinfunction "1_1") (pintype "passive"))
      (node (ref "R120") (pin "2") (pinfunction "2_2") (pintype "passive"))
      (node (ref "R121") (pin "1") (pinfunction "1_1") (pintype "passive"))
      (node (ref "R123") (pin "1") (pinfunction "1_1") (pintype "passive"))
      (node (ref "R124") (pin "1") (pinfunction "1_1") (pintype "passive"))
      (node (ref "R15") (pin "2") (pinfunction "2_2") (pintype "passive"))
      (node (ref "R25") (pin "1") (pinfunction "1_1") (pintype "passive"))
      (node (ref "R26") (pin "1") (pinfunction "1_1") (pintype "passive"))
      (node (ref "R3") (pin "5") (pinfunction "2_5") (pintype "passive"))
      (node (ref "R3") (pin "6") (pinfunction "2_6") (pintype "passive"))
      (node (ref "S1") (pin "3") (pinfunction "NO_3") (pintype "bidirectional"))
      (node (ref "THERM6") (pin "1") (pinfunction "1_1") (pintype "passive"))
      (node (ref "U$12") (pin "1") (pinfunction "GND_1") (pintype "bidirectional"))
      (node (ref "U$12") (pin "5") (pinfunction "PG_5") (pintype "bidirectional"))
      (node (ref "U$12") (pin "P$2_GND") (pinfunction "GND_P$2_GND") (pintype "bidirectional"))
      (node (ref "U$12") (pin "P$3_GND") (pinfunction "GND_P$3_GND") (pintype "bidirectional"))
      (node (ref "U$12") (pin "THERMAL_GND") (pinfunction "GND_THERMAL_GND") (pintype "bidirectional"))
      (node (ref "U$57") (pin "GND1") (pinfunction "GND1_GND1") (pintype "bidirectional"))
      (node (ref "U$57") (pin "GND2") (pinfunction "GND2_GND2") (pintype "bidirectional"))
      (node (ref "U$57") (pin "GND3") (pinfunction "GND3_GND3") (pintype "bidirectional"))
      (node (ref "U$6") (pin "10") (pinfunction "PIN10(GND)_10") (pintype "bidirectional"))
      (node (ref "U$6") (pin "15") (pinfunction "PIN15(GND)_15") (pintype "bidirectional"))
      (node (ref "U$6") (pin "16") (pinfunction "PIN16(GND)_16") (pintype "bidirectional"))
      (node (ref "U$6") (pin "17") (pinfunction "COM3/I2C_ADDR_17") (pintype "bidirectional"))
      (node (ref "U$6") (pin "18") (pinfunction "COM2(GND)_18") (pintype "bidirectional"))
      (node (ref "U$6") (pin "2") (pinfunction "GND_2") (pintype "power_in"))
      (node (ref "U$6") (pin "25") (pinfunction "GND_25") (pintype "power_in"))
      (node (ref "U1") (pin "11") (pinfunction "GND_11") (pintype "bidirectional"))
      (node (ref "U1") (pin "16") (pinfunction "NC_16") (pintype "bidirectional"))
      (node (ref "U1") (pin "17") (pinfunction "PGND_PAD_17") (pintype "bidirectional"))
      (node (ref "U1") (pin "3") (pinfunction "1_PGND_3") (pintype "bidirectional"))
      (node (ref "U1") (pin "4") (pinfunction "2_PGND_4") (pintype "bidirectional"))
      (node (ref "U1") (pin "5") (pinfunction "3_PGND_5") (pintype "bidirectional"))
      (node (ref "U1") (pin "8") (pinfunction "SYNC_8") (pintype "bidirectional"))
      (node (ref "U1") (pin "PAD_1") (pinfunction "PGND_PAD_PAD_1") (pintype "bidirectional"))
      (node (ref "U1") (pin "PAD_2") (pinfunction "PGND_PAD_PAD_2") (pintype "bidirectional"))
      (node (ref "U1") (pin "PAD_3") (pinfunction "PGND_PAD_PAD_3") (pintype "bidirectional"))
      (node (ref "U1") (pin "PAD_4") (pinfunction "PGND_PAD_PAD_4") (pintype "bidirectional"))
      (node (ref "U1") (pin "PAD_5") (pinfunction "PGND_PAD_PAD_5") (pintype "bidirectional"))
      (node (ref "U1") (pin "PAD_6") (pinfunction "PGND_PAD_PAD_6") (pintype "bidirectional"))
      (node (ref "U16") (pin "P$10") (pinfunction "VSS1_P$10") (pintype "bidirectional"))
      (node (ref "U16") (pin "P$11") (pinfunction "VSS2_P$11") (pintype "bidirectional"))
      (node (ref "U16") (pin "P$21") (pinfunction "THERMAL_P$21") (pintype "bidirectional"))
      (node (ref "U3") (pin "10") (pinfunction "PGND2_10") (pintype "power_in"))
      (node (ref "U3") (pin "18") (pinfunction "GND_18") (pintype "power_in"))
      (node (ref "U3") (pin "3") (pinfunction "PGND1_3") (pintype "power_in"))
      (node (ref "U3") (pin "4") (pinfunction "PGND1_4") (pintype "power_in"))
      (node (ref "U3") (pin "9") (pinfunction "PGND2_9") (pintype "power_in"))
      (node (ref "U5") (pin "1") (pinfunction "A0_1") (pintype "bidirectional"))
      (node (ref "U5") (pin "12") (pinfunction "GND_12") (pintype "bidirectional"))
      (node (ref "U5") (pin "2") (pinfunction "A1_2") (pintype "bidirectional"))
      (node (ref "U5") (pin "21") (pinfunction "A2_21") (pintype "bidirectional"))
    )
    (net (code "12") (name "I2CMUX_~{RST}") (class "Default")
      (node (ref "R49") (pin "1") (pinfunction "1_1") (pintype "passive"))
      (node (ref "U$57") (pin "17-A3/TX4/SDA1") (pinfunction "17-A3/TX4/SDA1_17-A3/TX4/SDA1") (pintype "bidirectional"))
      (node (ref "U5") (pin "3") (pinfunction "~{RST}_3") (pintype "bidirectional"))
    )
    (net (code "13") (name "IMU_NRESET_3V") (class "Default")
      (node (ref "D1") (pin "A") (pinfunction "A_A") (pintype "passive"))
      (node (ref "R4") (pin "2") (pinfunction "2_2") (pintype "passive"))
      (node (ref "U$6") (pin "11") (pinfunction "NRESET_11") (pintype "bidirectional"))
    )
    (net (code "14") (name "IMU_RESET") (class "Default")
      (node (ref "D1") (pin "C") (pinfunction "C_C") (pintype "passive"))
      (node (ref "U$57") (pin "16-A2/RX4/SCL1") (pinfunction "16-A2/RX4/SCL1_16-A2/RX4/SCL1") (pintype "bidirectional"))
    )
    (net (code "15") (name "INT_3V") (class "Default")
      (node (ref "U$6") (pin "14") (pinfunction "INT_14") (pintype "output"))
    )
    (net (code "16") (name "LMIN1") (class "Default")
      (node (ref "U$57") (pin "7-RX2/OUT1A") (pinfunction "7-OUT1A/RX2_7-RX2/OUT1A") (pintype "bidirectional"))
      (node (ref "U3") (pin "17") (pinfunction "BIN1_17") (pintype "input"))
    )
    (net (code "17") (name "LMIN2") (class "Default")
      (node (ref "U$57") (pin "8-TX2/IN1") (pinfunction "8-IN1/TX2_8-TX2/IN1") (pintype "bidirectional"))
      (node (ref "U3") (pin "16") (pinfunction "BIN2_16") (pintype "input"))
    )
    (net (code "18") (name "LMOUT+") (class "Default")
      (node (ref "MOTORL") (pin "1") (pinfunction "1_1") (pintype "passive"))
      (node (ref "U3") (pin "11") (pinfunction "BOUT1_11") (pintype "output"))
      (node (ref "U3") (pin "12") (pinfunction "BOUT1_12") (pintype "output"))
    )
    (net (code "19") (name "LMOUT-") (class "Default")
      (node (ref "MOTORL") (pin "6") (pinfunction "6_6") (pintype "passive"))
      (node (ref "U3") (pin "7") (pinfunction "BOUT2_7") (pintype "output"))
      (node (ref "U3") (pin "8") (pinfunction "BOUT2_8") (pintype "output"))
    )
    (net (code "20") (name "MOT_EN") (class "Default")
      (node (ref "R2") (pin "2") (pinfunction "2_2") (pintype "passive"))
      (node (ref "U$12") (pin "6") (pinfunction "EN_6") (pintype "bidirectional"))
      (node (ref "U$57") (pin "5-IN2") (pinfunction "5-IN2_5-IN2") (pintype "bidirectional"))
    )
    (net (code "21") (name "NEOPIXEL") (class "Default")
      (node (ref "R5") (pin "2") (pinfunction "2_2") (pintype "passive"))
      (node (ref "U$57") (pin "10-CS/MQSR") (pinfunction "10-CS_10-CS/MQSR") (pintype "bidirectional"))
    )
    (net (code "22") (name "Net-(C8-P$2)") (class "Default")
      (node (ref "C8") (pin "2") (pinfunction "P$2_2") (pintype "passive"))
      (node (ref "R14") (pin "2") (pinfunction "2_2") (pintype "passive"))
      (node (ref "R15") (pin "1") (pinfunction "1_1") (pintype "passive"))
      (node (ref "U$12") (pin "3") (pinfunction "FB_3") (pintype "bidirectional"))
    )
    (net (code "23") (name "Net-(CHRG-PadC)") (class "Default")
      (node (ref "CHRG") (pin "C") (pinfunction "C_C") (pintype "passive"))
      (node (ref "R21") (pin "2") (pinfunction "2_2") (pintype "passive"))
    )
    (net (code "24") (name "Net-(DONE-PadC)") (class "Default")
      (node (ref "DONE") (pin "C") (pinfunction "C_C") (pintype "passive"))
      (node (ref "R122") (pin "2") (pinfunction "2_2") (pintype "passive"))
    )
    (net (code "25") (name "Net-(L2-2)") (class "Default")
      (node (ref "L2") (pin "P$2") (pinfunction "2_P$2") (pintype "passive"))
      (node (ref "U$12") (pin "7") (pinfunction "SW_7") (pintype "bidirectional"))
    )
    (net (code "26") (name "Net-(L3-2)") (class "Default")
      (node (ref "L3") (pin "P$2") (pinfunction "2_P$2") (pintype "passive"))
      (node (ref "U1") (pin "1") (pinfunction "1_SW_1") (pintype "bidirectional"))
      (node (ref "U1") (pin "2") (pinfunction "2_SW_2") (pintype "bidirectional"))
    )
    (net (code "27") (name "Net-(LBO-PadA)") (class "Default")
      (node (ref "LBO") (pin "A") (pinfunction "A_A") (pintype "passive"))
      (node (ref "T1") (pin "C") (pinfunction "C_C") (pintype "passive"))
    )
    (net (code "28") (name "Net-(LBO-PadC)") (class "Default")
      (node (ref "LBO") (pin "C") (pinfunction "C_C") (pintype "passive"))
      (node (ref "R121") (pin "2") (pinfunction "2_2") (pintype "passive"))
    )
    (net (code "29") (name "Net-(NEOPIXEL-DIN)") (class "Default")
      (node (ref "NEOPIXEL") (pin "4") (pinfunction "DIN_4") (pintype "input"))
      (node (ref "R5") (pin "1") (pinfunction "1_1") (pintype "passive"))
    )
    (net (code "30") (name "Net-(PWR-PadA)") (class "Default")
      (node (ref "PWR") (pin "A") (pinfunction "A_A") (pintype "passive"))
      (node (ref "R22") (pin "2") (pinfunction "2_2") (pintype "passive"))
    )
    (net (code "31") (name "Net-(Q1-B)") (class "Default")
      (node (ref "Q1") (pin "1") (pinfunction "B_1") (pintype "passive"))
      (node (ref "R6") (pin "1") (pinfunction "1_1") (pintype "passive"))
    )
    (net (code "32") (name "Net-(Q1-C)") (class "Default")
      (node (ref "J4") (pin "5") (pinfunction "5_5") (pintype "passive"))
      (node (ref "Q1") (pin "3") (pinfunction "C_3") (pintype "passive"))
    )
    (net (code "33") (name "Net-(U$6-CAP)") (class "Default")
      (node (ref "C4") (pin "2") (pinfunction "2_2") (pintype "passive"))
      (node (ref "U$6") (pin "9") (pinfunction "CAP_9") (pintype "passive"))
    )
    (net (code "34") (name "Net-(U$6-XIN32)") (class "Default")
      (node (ref "C1") (pin "2") (pinfunction "2_2") (pintype "passive"))
      (node (ref "U$6") (pin "27") (pinfunction "XIN32_27") (pintype "input"))
      (node (ref "X2") (pin "P$2") (pinfunction "P$2_P$2") (pintype "bidirectional"))
    )
    (net (code "35") (name "Net-(U$6-XOUT32)") (class "Default")
      (node (ref "C2") (pin "2") (pinfunction "2_2") (pintype "passive"))
      (node (ref "U$6") (pin "26") (pinfunction "XOUT32_26") (pintype "output"))
      (node (ref "X2") (pin "P$1") (pinfunction "P$1_P$1") (pintype "bidirectional"))
    )
    (net (code "36") (name "Net-(U1-FB)") (class "Default")
      (node (ref "R24") (pin "1") (pinfunction "1_1") (pintype "passive"))
      (node (ref "R25") (pin "2") (pinfunction "2_2") (pintype "passive"))
      (node (ref "U1") (pin "12") (pinfunction "FB_12") (pintype "bidirectional"))
    )
    (net (code "37") (name "Net-(U1-LBI)") (class "Default")
      (node (ref "R26") (pin "2") (pinfunction "2_2") (pintype "passive"))
      (node (ref "R27") (pin "1") (pinfunction "1_1") (pintype "passive"))
      (node (ref "U1") (pin "7") (pinfunction "LBI_7") (pintype "bidirectional"))
    )
    (net (code "38") (name "Net-(U1-LBO)") (class "Default")
      (node (ref "T1") (pin "B") (pinfunction "B_B") (pintype "passive"))
      (node (ref "U1") (pin "10") (pinfunction "LBO_10") (pintype "bidirectional"))
    )
    (net (code "39") (name "Net-(U16-PROG1)") (class "Default")
      (node (ref "R123") (pin "2") (pinfunction "2_2") (pintype "passive"))
      (node (ref "U16") (pin "P$13") (pinfunction "PROG1_P$13") (pintype "bidirectional"))
    )
    (net (code "40") (name "Net-(U16-PROG3)") (class "Default")
      (node (ref "R124") (pin "2") (pinfunction "2_2") (pintype "passive"))
      (node (ref "U16") (pin "P$12") (pinfunction "PROG3_P$12") (pintype "bidirectional"))
    )
    (net (code "41") (name "Net-(U16-STAT1{slash}LBO)") (class "Default")
      (node (ref "R21") (pin "1") (pinfunction "1_1") (pintype "passive"))
      (node (ref "U16") (pin "P$8") (pinfunction "STAT1/LBO_P$8") (pintype "bidirectional"))
    )
    (net (code "42") (name "Net-(U16-STAT2)") (class "Default")
      (node (ref "R122") (pin "1") (pinfunction "1_1") (pintype "passive"))
      (node (ref "U16") (pin "P$7") (pinfunction "STAT2_P$7") (pintype "bidirectional"))
    )
    (net (code "43") (name "Net-(U16-THERM)") (class "Default")
      (node (ref "THERM6") (pin "2") (pinfunction "2_2") (pintype "passive"))
      (node (ref "U16") (pin "P$5") (pinfunction "THERM_P$5") (pintype "bidirectional"))
    )
    (net (code "44") (name "Net-(U16-VPCC)") (class "Default")
      (node (ref "R119") (pin "1") (pinfunction "1_1") (pintype "passive"))
      (node (ref "R120") (pin "1") (pinfunction "1_1") (pintype "passive"))
      (node (ref "U16") (pin "P$2") (pinfunction "VPCC_P$2") (pintype "bidirectional"))
    )
    (net (code "45") (name "PI_START") (class "Default")
      (node (ref "R6") (pin "2") (pinfunction "2_2") (pintype "passive"))
      (node (ref "U$57") (pin "9-OUT1C") (pinfunction "9-OUT1C_9-OUT1C") (pintype "bidirectional"))
    )
    (net (code "46") (name "PS0_3V") (class "Default")
      (node (ref "R3") (pin "3") (pinfunction "1_3") (pintype "passive"))
      (node (ref "U$6") (pin "6") (pinfunction "PS0_6") (pintype "input"))
    )
    (net (code "47") (name "PS1_3V") (class "Default")
      (node (ref "R3") (pin "4") (pinfunction "1_4") (pintype "passive"))
      (node (ref "U$6") (pin "5") (pinfunction "PS1_5") (pintype "input"))
    )
    (net (code "48") (name "PWML") (class "Default")
      (node (ref "U$57") (pin "23-A9/CRX1/CCLK1") (pinfunction "23-A9/CRX1/MCLK1_23-A9/CRX1/CCLK1") (pintype "bidirectional"))
      (node (ref "U3") (pin "15") (pinfunction "PWMB_15") (pintype "input"))
    )
    (net (code "49") (name "PWMR") (class "Default")
      (node (ref "U$57") (pin "4-BCLK2") (pinfunction "4-BCLK1_4-BCLK2") (pintype "bidirectional"))
      (node (ref "U3") (pin "23") (pinfunction "PWMA_23") (pintype "input"))
    )
    (net (code "50") (name "RMIN1") (class "Default")
      (node (ref "U$57") (pin "0-RX1") (pinfunction "0-RX1/CRX2_0-RX1") (pintype "bidirectional"))
      (node (ref "U3") (pin "21") (pinfunction "AIN1_21") (pintype "input"))
    )
    (net (code "51") (name "RMIN2") (class "Default")
      (node (ref "U$57") (pin "1-TX1") (pinfunction "1-TX1/CTX2_1-TX1") (pintype "bidirectional"))
      (node (ref "U3") (pin "22") (pinfunction "AIN2_22") (pintype "input"))
    )
    (net (code "52") (name "RMOUT+") (class "Default")
      (node (ref "MOTORR") (pin "1") (pinfunction "1_1") (pintype "passive"))
      (node (ref "U3") (pin "1") (pinfunction "AOUT1_1") (pintype "output"))
      (node (ref "U3") (pin "2") (pinfunction "AOUT1_2") (pintype "output"))
    )
    (net (code "53") (name "RMOUT-") (class "Default")
      (node (ref "MOTORR") (pin "6") (pinfunction "6_6") (pintype "passive"))
      (node (ref "U3") (pin "5") (pinfunction "AOUT2_5") (pintype "output"))
      (node (ref "U3") (pin "6") (pinfunction "AOUT2_6") (pintype "output"))
    )
    (net (code "54") (name "RPI_RX") (class "Default")
      (node (ref "J4") (pin "1") (pinfunction "1_1") (pintype "passive"))
      (node (ref "U$57") (pin "14-A0/TX3/S-PFI_OUT") (pinfunction "14-A0/TX3/S-PDIF_IN_14-A0/TX3/S-PFI_OUT") (pintype "bidirectional"))
    )
    (net (code "55") (name "RPI_TX") (class "Default")
      (node (ref "J4") (pin "2") (pinfunction "2_2") (pintype "passive"))
      (node (ref "U$57") (pin "15-A1/RX3/S-PDIF_IN") (pinfunction "15-A1/RX3/SPDIF_IN_15-A1/RX3/S-PDIF_IN") (pintype "bidirectional"))
    )
    (net (code "56") (name "SCL0") (class "Default")
      (node (ref "JD0") (pin "4") (pinfunction "4_4") (pintype "passive"))
      (node (ref "R29") (pin "2") (pinfunction "2_2") (pintype "passive"))
      (node (ref "U5") (pin "5") (pinfunction "SC0_5") (pintype "bidirectional"))
    )
    (net (code "57") (name "SCL1") (class "Default")
      (node (ref "JD1") (pin "4") (pinfunction "4_4") (pintype "passive"))
      (node (ref "R31") (pin "2") (pinfunction "2_2") (pintype "passive"))
      (node (ref "U5") (pin "7") (pinfunction "SC1_7") (pintype "bidirectional"))
    )
    (net (code "58") (name "SCL2") (class "Default")
      (node (ref "JD2") (pin "4") (pinfunction "4_4") (pintype "passive"))
      (node (ref "R33") (pin "2") (pinfunction "2_2") (pintype "passive"))
      (node (ref "U5") (pin "9") (pinfunction "SC2_9") (pintype "bidirectional"))
    )
    (net (code "59") (name "SCL3") (class "Default")
      (node (ref "JD3") (pin "4") (pinfunction "4_4") (pintype "passive"))
      (node (ref "R35") (pin "2") (pinfunction "2_2") (pintype "passive"))
      (node (ref "U5") (pin "11") (pinfunction "SC3_11") (pintype "bidirectional"))
    )
    (net (code "60") (name "SCL4") (class "Default")
      (node (ref "JD4") (pin "4") (pinfunction "4_4") (pintype "passive"))
      (node (ref "R37") (pin "2") (pinfunction "2_2") (pintype "passive"))
      (node (ref "U5") (pin "14") (pinfunction "SC4_14") (pintype "bidirectional"))
    )
    (net (code "61") (name "SCL5") (class "Default")
      (node (ref "JD5") (pin "4") (pinfunction "4_4") (pintype "passive"))
      (node (ref "R39") (pin "2") (pinfunction "2_2") (pintype "passive"))
      (node (ref "U5") (pin "16") (pinfunction "SC5_16") (pintype "bidirectional"))
    )
    (net (code "62") (name "SCL6") (class "Default")
      (node (ref "JD6") (pin "4") (pinfunction "4_4") (pintype "passive"))
      (node (ref "R41") (pin "2") (pinfunction "2_2") (pintype "passive"))
      (node (ref "U5") (pin "18") (pinfunction "SC6_18") (pintype "bidirectional"))
    )
    (net (code "63") (name "SCL_MAIN") (class "Default")
      (node (ref "IC1") (pin "9") (pinfunction "SCL_9") (pintype "bidirectional"))
      (node (ref "R9") (pin "8") (pinfunction "2_8") (pintype "passive"))
      (node (ref "U$57") (pin "19-A5/SCL0") (pinfunction "19-A5/SCL0_19-A5/SCL0") (pintype "bidirectional"))
      (node (ref "U$6") (pin "19") (pinfunction "COM1/SCL/RX_19") (pintype "bidirectional"))
      (node (ref "U5") (pin "22") (pinfunction "SCL_22") (pintype "bidirectional"))
    )
    (net (code "64") (name "SDA0") (class "Default")
      (node (ref "JD0") (pin "3") (pinfunction "3_3") (pintype "passive"))
      (node (ref "R28") (pin "2") (pinfunction "2_2") (pintype "passive"))
      (node (ref "U5") (pin "4") (pinfunction "SD0_4") (pintype "bidirectional"))
    )
    (net (code "65") (name "SDA1") (class "Default")
      (node (ref "JD1") (pin "3") (pinfunction "3_3") (pintype "passive"))
      (node (ref "R30") (pin "2") (pinfunction "2_2") (pintype "passive"))
      (node (ref "U5") (pin "6") (pinfunction "SD1_6") (pintype "bidirectional"))
    )
    (net (code "66") (name "SDA2") (class "Default")
      (node (ref "JD2") (pin "3") (pinfunction "3_3") (pintype "passive"))
      (node (ref "R32") (pin "2") (pinfunction "2_2") (pintype "passive"))
      (node (ref "U5") (pin "8") (pinfunction "SD2_8") (pintype "bidirectional"))
    )
    (net (code "67") (name "SDA3") (class "Default")
      (node (ref "JD3") (pin "3") (pinfunction "3_3") (pintype "passive"))
      (node (ref "R34") (pin "2") (pinfunction "2_2") (pintype "passive"))
      (node (ref "U5") (pin "10") (pinfunction "SD3_10") (pintype "bidirectional"))
    )
    (net (code "68") (name "SDA4") (class "Default")
      (node (ref "JD4") (pin "3") (pinfunction "3_3") (pintype "passive"))
      (node (ref "R36") (pin "2") (pinfunction "2_2") (pintype "passive"))
      (node (ref "U5") (pin "13") (pinfunction "SD4_13") (pintype "bidirectional"))
    )
    (net (code "69") (name "SDA5") (class "Default")
      (node (ref "JD5") (pin "3") (pinfunction "3_3") (pintype "passive"))
      (node (ref "R38") (pin "2") (pinfunction "2_2") (pintype "passive"))
      (node (ref "U5") (pin "15") (pinfunction "SD5_15") (pintype "bidirectional"))
    )
    (net (code "70") (name "SDA6") (class "Default")
      (node (ref "JD6") (pin "3") (pinfunction "3_3") (pintype "passive"))
      (node (ref "R40") (pin "2") (pinfunction "2_2") (pintype "passive"))
      (node (ref "U5") (pin "17") (pinfunction "SD6_17") (pintype "bidirectional"))
    )
    (net (code "71") (name "SDA_MAIN") (class "Default")
      (node (ref "IC1") (pin "8") (pinfunction "SDA_8") (pintype "bidirectional"))
      (node (ref "R9") (pin "5") (pinfunction "2_5") (pintype "passive"))
      (node (ref "U$57") (pin "18-A4/SDA0") (pinfunction "18-A4/SDA0_18-A4/SDA0") (pintype "bidirectional"))
      (node (ref "U$6") (pin "20") (pinfunction "COM0/SDA/TX_20") (pintype "bidirectional"))
      (node (ref "U5") (pin "23") (pinfunction "SDA_23") (pintype "bidirectional"))
    )
    (net (code "72") (name "STBY") (class "Default")
      (node (ref "R16") (pin "1") (pinfunction "1_1") (pintype "passive"))
      (node (ref "U$57") (pin "6-OUT1D") (pinfunction "6-OUT1D_6-OUT1D") (pintype "bidirectional"))
      (node (ref "U3") (pin "19") (pinfunction "STBY_19") (pintype "input"))
    )
    (net (code "73") (name "VBAT") (class "Default")
      (node (ref "C13") (pin "1") (pinfunction "1_1") (pintype "passive"))
      (node (ref "C15") (pin "1") (pinfunction "1_1") (pintype "passive"))
      (node (ref "C3") (pin "1") (pinfunction "P$1_1") (pintype "passive"))
      (node (ref "C7") (pin "1") (pinfunction "P$1_1") (pintype "passive"))
      (node (ref "L2") (pin "P$1") (pinfunction "1_P$1") (pintype "passive"))
      (node (ref "L3") (pin "P$1") (pinfunction "1_P$1") (pintype "passive"))
      (node (ref "R1") (pin "1") (pinfunction "1_1") (pintype "passive"))
      (node (ref "R2") (pin "1") (pinfunction "1_1") (pintype "passive"))
      (node (ref "R27") (pin "2") (pinfunction "2_2") (pintype "passive"))
      (node (ref "T1") (pin "E") (pinfunction "E_E") (pintype "passive"))
      (node (ref "U$12") (pin "4") (pinfunction "ILIM_4") (pintype "bidirectional"))
      (node (ref "U$12") (pin "8") (pinfunction "VIN_8") (pintype "bidirectional"))
      (node (ref "U1") (pin "6") (pinfunction "VBAT_6") (pintype "bidirectional"))
      (node (ref "U16") (pin "P$1") (pinfunction "VOUT1_P$1") (pintype "bidirectional"))
      (node (ref "U16") (pin "P$20") (pinfunction "VOUT2_P$20") (pintype "bidirectional"))
    )
    (net (code "74") (name "VBAT_IN") (class "Default")
      (node (ref "B1") (pin "2") (pinfunction "+_2") (pintype "passive"))
      (node (ref "C49") (pin "1") (pinfunction "1_1") (pintype "passive"))
      (node (ref "IC1") (pin "1") (pinfunction "IN+_1") (pintype "bidirectional"))
      (node (ref "IC1") (pin "12") (pinfunction "VBUS_12") (pintype "power_in"))
      (node (ref "IC1") (pin "2") (pinfunction "IN+_2") (pintype "bidirectional"))
      (node (ref "IC1") (pin "3") (pinfunction "IN+_3") (pintype "bidirectional"))
      (node (ref "JP1") (pin "1") (pinfunction "1_1") (pintype "passive"))
      (node (ref "R11") (pin "2") (pinfunction "2_2") (pintype "passive"))
    )
    (net (code "75") (name "VBAT_MEASURE") (class "Default")
      (node (ref "R11") (pin "1") (pinfunction "1_1") (pintype "passive"))
      (node (ref "R12") (pin "2") (pinfunction "2_2") (pintype "passive"))
      (node (ref "U$57") (pin "22-A8/CTX1") (pinfunction "22-A8/CTX1_22-A8/CTX1") (pintype "bidirectional"))
    )
    (net (code "76") (name "VBUS") (class "Default")
      (node (ref "C17") (pin "1") (pinfunction "1_1") (pintype "passive"))
      (node (ref "CHRG") (pin "A") (pinfunction "A_A") (pintype "passive"))
      (node (ref "CN4") (pin "VBUS") (pinfunction "VBUS_VBUS") (pintype "power_in"))
      (node (ref "DONE") (pin "A") (pinfunction "A_A") (pintype "passive"))
      (node (ref "R119") (pin "2") (pinfunction "2_2") (pintype "passive"))
      (node (ref "R13") (pin "1") (pinfunction "1_1") (pintype "passive"))
      (node (ref "U16") (pin "P$17") (pinfunction "CE_P$17") (pintype "bidirectional"))
      (node (ref "U16") (pin "P$18") (pinfunction "VIN1_P$18") (pintype "bidirectional"))
      (node (ref "U16") (pin "P$19") (pinfunction "VIN2_P$19") (pintype "bidirectional"))
      (node (ref "U16") (pin "P$3") (pinfunction "SEL_P$3") (pintype "bidirectional"))
      (node (ref "U16") (pin "P$4") (pinfunction "PROG2_P$4") (pintype "bidirectional"))
      (node (ref "U16") (pin "P$9") (pinfunction "/TE_P$9") (pintype "bidirectional"))
    )
    (net (code "77") (name "VMOTOR") (class "Default")
      (node (ref "C11") (pin "1") (pinfunction "P$1_1") (pintype "passive"))
      (node (ref "Q2") (pin "2") (pinfunction "S_2") (pintype "passive"))
      (node (ref "U3") (pin "13") (pinfunction "VM_13") (pintype "power_in"))
      (node (ref "U3") (pin "14") (pinfunction "VM_14") (pintype "power_in"))
      (node (ref "U3") (pin "24") (pinfunction "VM_24") (pintype "power_in"))
    )
    (net (code "78") (name "V_PWR") (class "Default")
      (node (ref "IC1") (pin "14") (pinfunction "IN-_14") (pintype "bidirectional"))
      (node (ref "IC1") (pin "15") (pinfunction "IN-_15") (pintype "bidirectional"))
      (node (ref "IC1") (pin "16") (pinfunction "IN-_16") (pintype "bidirectional"))
      (node (ref "JP1") (pin "2") (pinfunction "2_2") (pintype "passive"))
      (node (ref "U16") (pin "P$14") (pinfunction "VBAT1_P$14") (pintype "bidirectional"))
      (node (ref "U16") (pin "P$15") (pinfunction "VBAT2_P$15") (pintype "bidirectional"))
      (node (ref "U16") (pin "P$16") (pinfunction "VBATSENS_P$16") (pintype "bidirectional"))
    )
    (net (code "79") (name "unconnected-(CN4-PadD+)") (class "Default")
      (node (ref "CN4") (pin "D+") (pinfunction "D+_D+") (pintype "bidirectional"))
    )
    (net (code "80") (name "unconnected-(CN4-PadD-)") (class "Default")
      (node (ref "CN4") (pin "D-") (pinfunction "D-_D-") (pintype "bidirectional"))
    )
    (net (code "81") (name "unconnected-(CN4-PadID)") (class "Default")
      (node (ref "CN4") (pin "ID") (pinfunction "ID_ID") (pintype "bidirectional"))
    )
    (net (code "82") (name "unconnected-(NEOPIXEL-DOUT-Pad2)") (class "Default")
      (node (ref "NEOPIXEL") (pin "2") (pinfunction "DOUT_2") (pintype "output"))
    )
    (net (code "83") (name "unconnected-(S1-NC-Pad1)") (class "Default")
      (node (ref "S1") (pin "1") (pinfunction "NC_1") (pintype "no_connect"))
    )
    (net (code "84") (name "unconnected-(U$6-PIN7(SWDIO)-Pad7)") (class "Default")
      (node (ref "U$6") (pin "7") (pinfunction "PIN7(SWDIO)_7") (pintype "bidirectional"))
    )
    (net (code "85") (name "unconnected-(U$57-12-MISO{slash}MQSL-Pad12-MIO{slash}MQSL)") (class "Default")
      (node (ref "U$57") (pin "12-MIO/MQSL") (pinfunction "12-MISO/MQSL_12-MIO/MQSL") (pintype "bidirectional"))
    )
    (net (code "86") (name "unconnected-(U$57-25-A11{slash}RX6{slash}SDA2-Pad25-A11{slash}SDA2)") (class "Default")
      (node (ref "U$57") (pin "25-A11/SDA2") (pinfunction "25-A11/RX6/SDA2_25-A11/SDA2") (pintype "bidirectional"))
    )
    (net (code "87") (name "unconnected-(U$57-32-OUT1B-Pad32-OUTB1)") (class "Default")
      (node (ref "U$57") (pin "32-OUTB1") (pinfunction "32-OUT1B_32-OUTB1") (pintype "bidirectional"))
    )
    (net (code "88") (name "unconnected-(U$57-Pad3V3-2)") (class "Default")
      (node (ref "U$57") (pin "3V3-2") (pinfunction "3V3-2_3V3-2") (pintype "bidirectional"))
    )
    (net (code "89") (name "unconnected-(U$57-Pad11-MOSI{slash}CTX1)") (class "Default")
      (node (ref "U$57") (pin "11-MOSI/CTX1") (pinfunction "11-MOSI/CTX1_11-MOSI/CTX1") (pintype "bidirectional"))
    )
    (net (code "90") (name "unconnected-(U$57-Pad24-A10{slash}TX6{slash}SCL2)") (class "Default")
      (node (ref "U$57") (pin "24-A10/TX6/SCL2") (pinfunction "24-A10/TX6/SCL2_24-A10/TX6/SCL2") (pintype "bidirectional"))
    )
    (net (code "91") (name "unconnected-(U$57-Pad26-A12{slash}MOSI1)") (class "Default")
      (node (ref "U$57") (pin "26-A12/MOSI1") (pinfunction "26-A12/MOSI1_26-A12/MOSI1") (pintype "bidirectional"))
    )
    (net (code "92") (name "unconnected-(U$57-Pad27-A13{slash}SCK1)") (class "Default")
      (node (ref "U$57") (pin "27-A13/SCK1") (pinfunction "27-A13/SCK1_27-A13/SCK1") (pintype "bidirectional"))
    )
    (net (code "93") (name "unconnected-(U$57-Pad28-RX7)") (class "Default")
      (node (ref "U$57") (pin "28-RX7") (pinfunction "28-RX7_28-RX7") (pintype "bidirectional"))
    )
    (net (code "94") (name "unconnected-(U$57-Pad29-TX7)") (class "Default")
      (node (ref "U$57") (pin "29-TX7") (pinfunction "29-TX7_29-TX7") (pintype "bidirectional"))
    )
    (net (code "95") (name "unconnected-(U$57-Pad30-CRX3)") (class "Default")
      (node (ref "U$57") (pin "30-CRX3") (pinfunction "30-CRX3_30-CRX3") (pintype "bidirectional"))
    )
    (net (code "96") (name "unconnected-(U$57-Pad31-CTX3)") (class "Default")
      (node (ref "U$57") (pin "31-CTX3") (pinfunction "31-CTX3_31-CTX3") (pintype "bidirectional"))
    )
    (net (code "97") (name "unconnected-(U$57-Pad33-MCLK2)") (class "Default")
      (node (ref "U$57") (pin "33-MCLK2") (pinfunction "33-MCLK2_33-MCLK2") (pintype "bidirectional"))
    )
    (net (code "98") (name "unconnected-(U$57-PadON{slash}OFF)") (class "Default")
      (node (ref "U$57") (pin "ON/OFF") (pinfunction "ON/OFF_ON/OFF") (pintype "bidirectional"))
    )
    (net (code "99") (name "unconnected-(U$57-PadPROGRAM)") (class "Default")
      (node (ref "U$57") (pin "PROGRAM") (pinfunction "PROGRAM_PROGRAM") (pintype "bidirectional"))
    )
    (net (code "100") (name "unconnected-(U$57-PadVBAT)") (class "Default")
      (node (ref "U$57") (pin "VBAT") (pinfunction "VBAT_VBAT") (pintype "bidirectional"))
    )
    (net (code "101") (name "unconnected-(U$57-PadVUSB)") (class "Default")
      (node (ref "U$57") (pin "VUSB") (pinfunction "VUSB_VUSB") (pintype "bidirectional"))
    )
    (net (code "102") (name "unconnected-(U5-SC7-Pad20)") (class "Default")
      (node (ref "U5") (pin "20") (pinfunction "SC7_20") (pintype "bidirectional"))
    )
    (net (code "103") (name "unconnected-(U5-SD7-Pad19)") (class "Default")
      (node (ref "U5") (pin "19") (pinfunction "SD7_19") (pintype "bidirectional"))
    )
    (net (code "104") (name "unconnected-(U16-{slash}PG-PadP$6)") (class "Default")
      (node (ref "U16") (pin "P$6") (pinfunction "/PG_P$6") (pintype "bidirectional"))
    )
  )
)
